# Led_Driver_90_B1.net
KiCad netlist of a schematic drawn in EAGLE
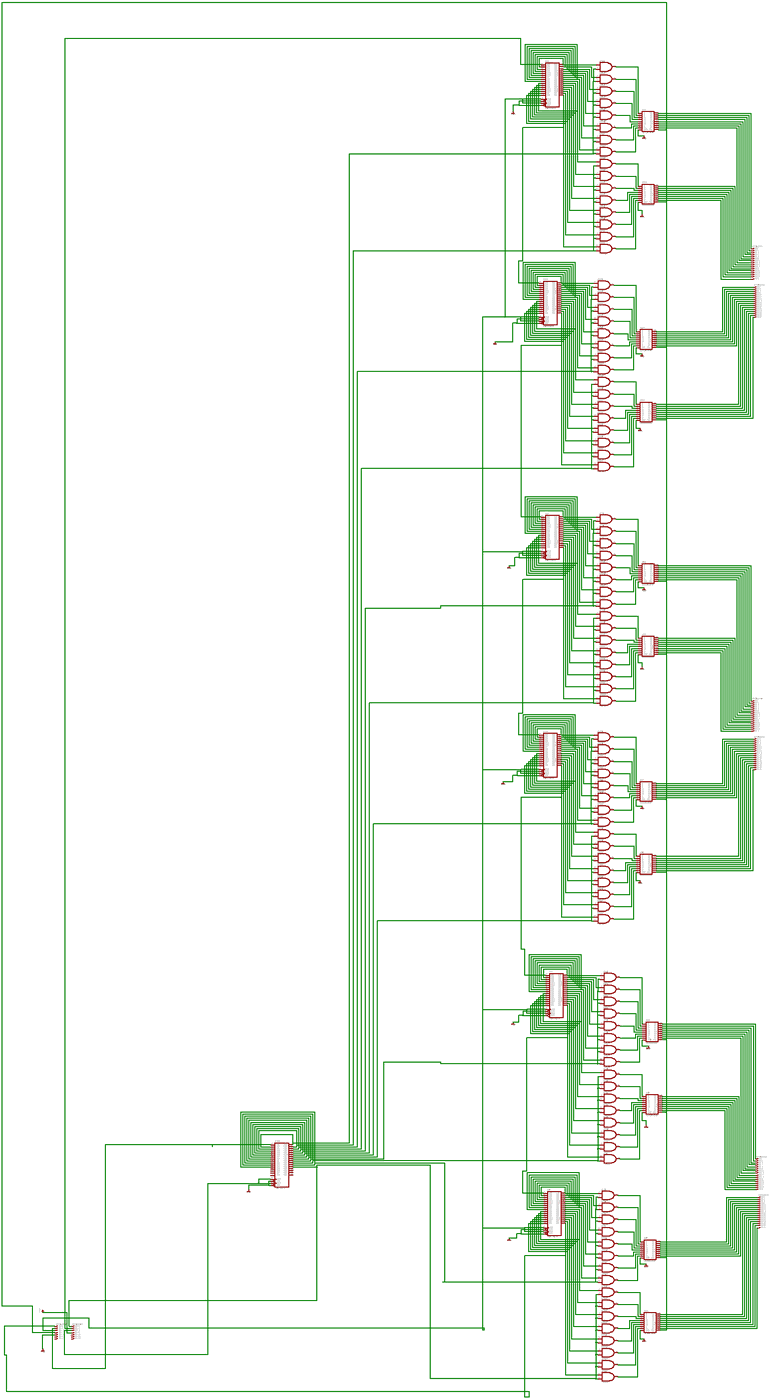
[diagram p0: schematic, sheet 1, overview]
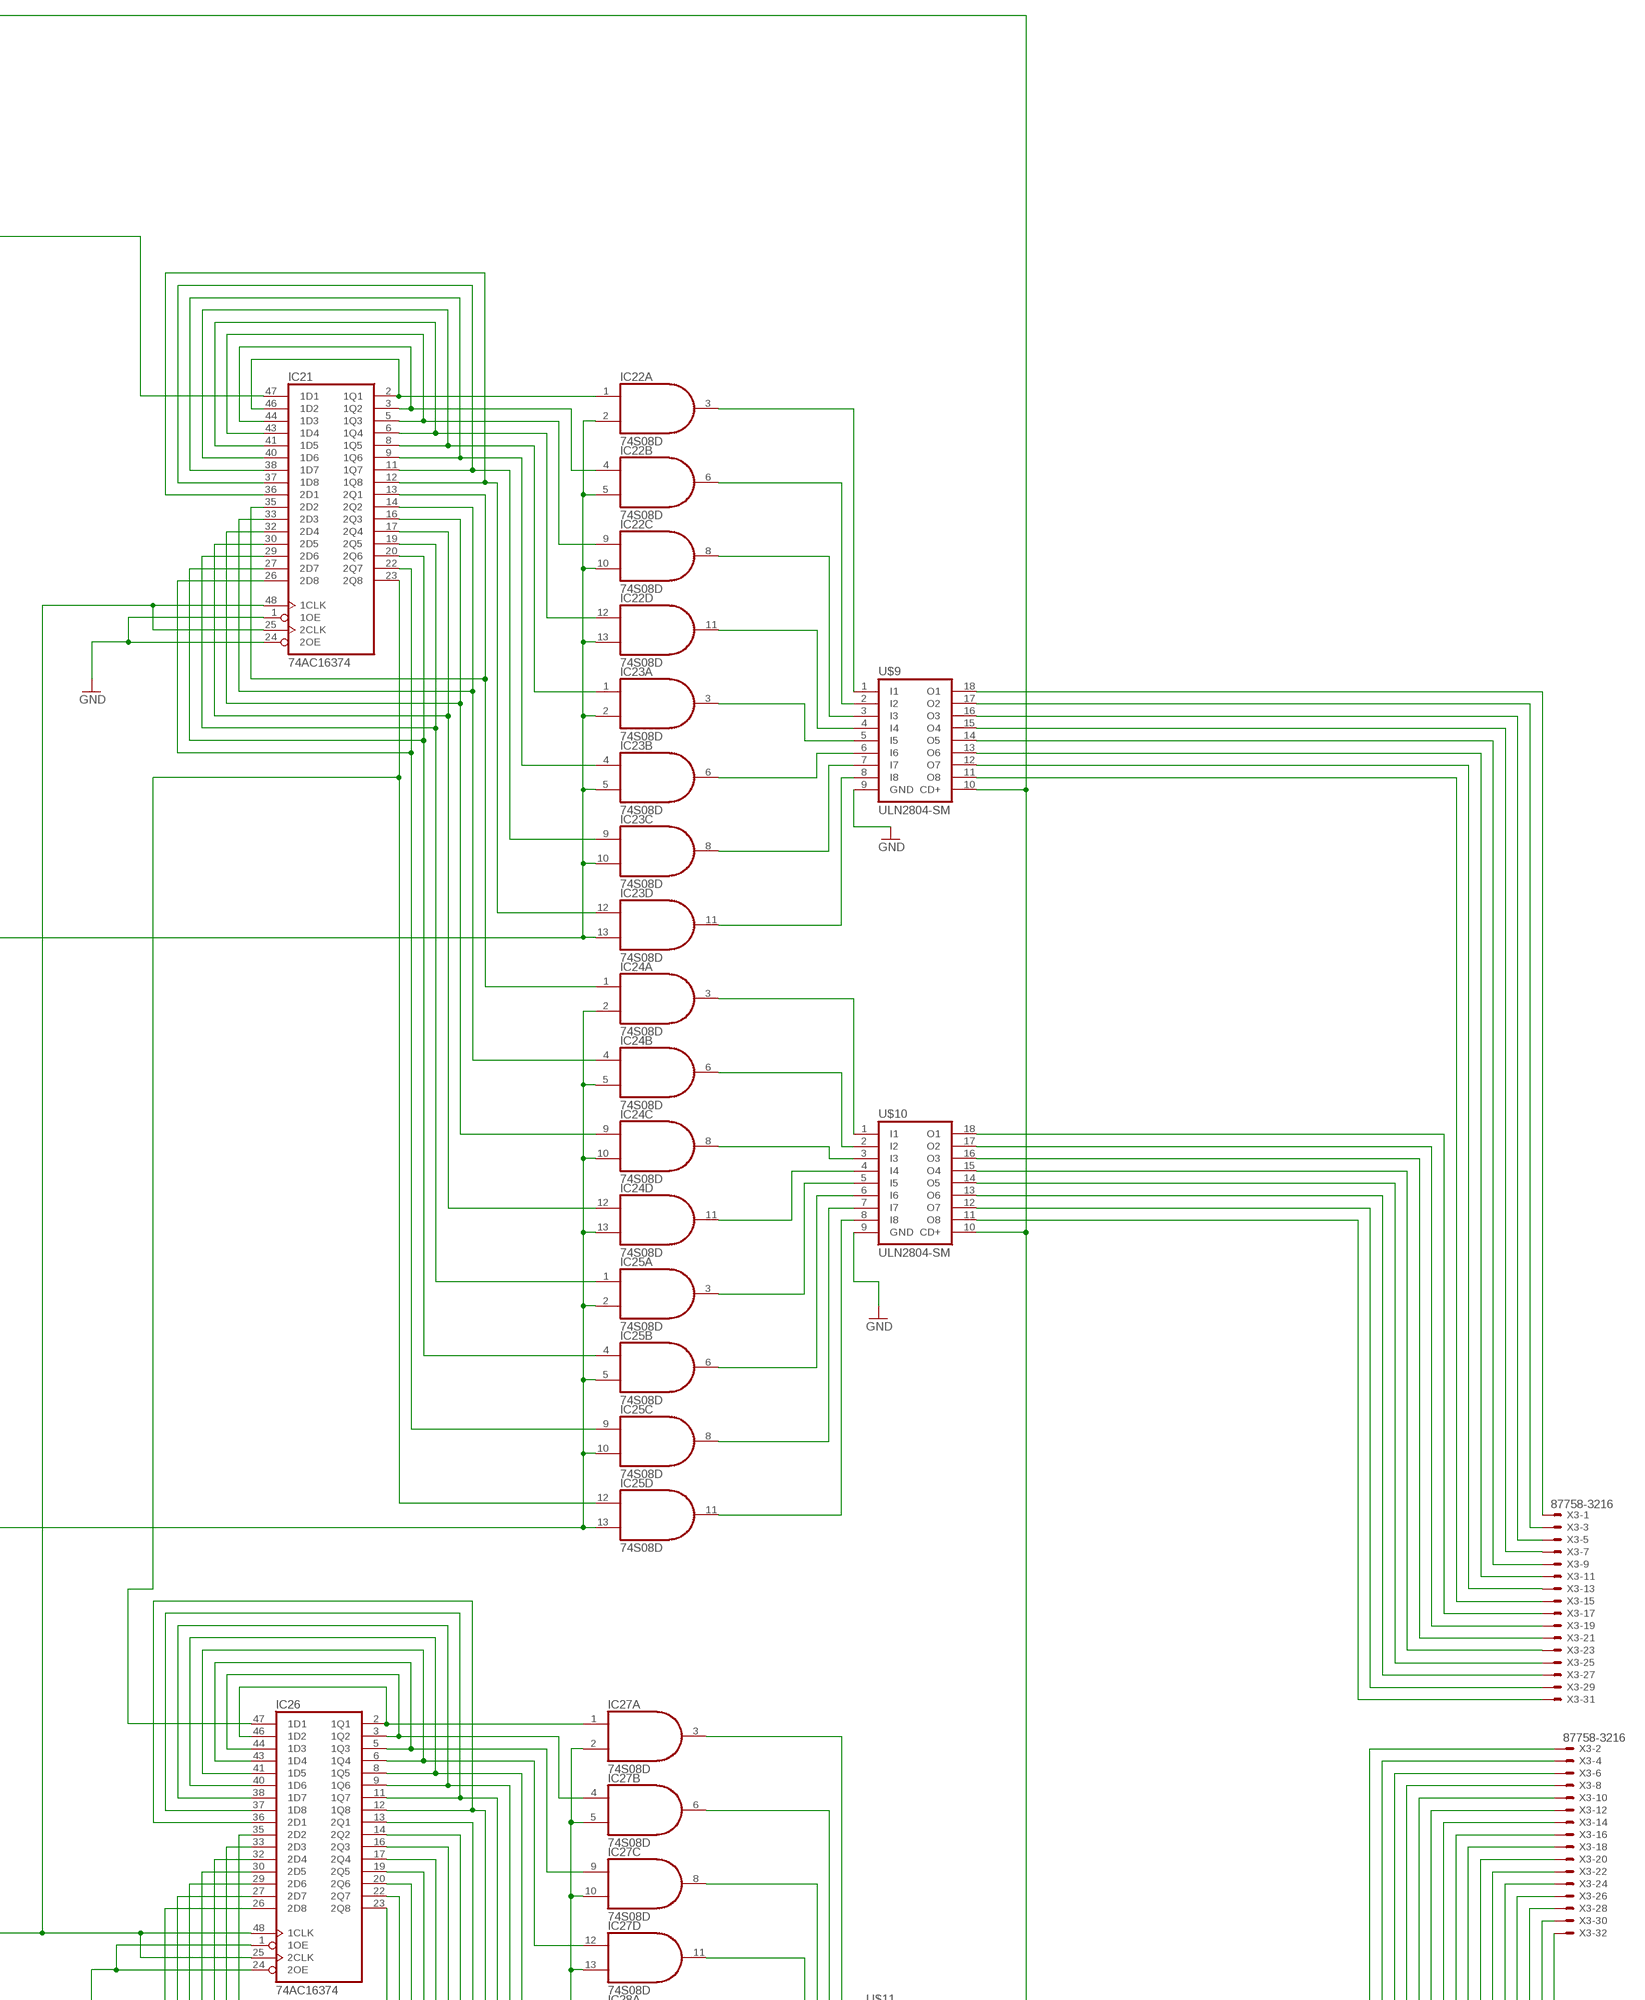
[diagram p1: schematic, sheet 1, part 1 of 9]
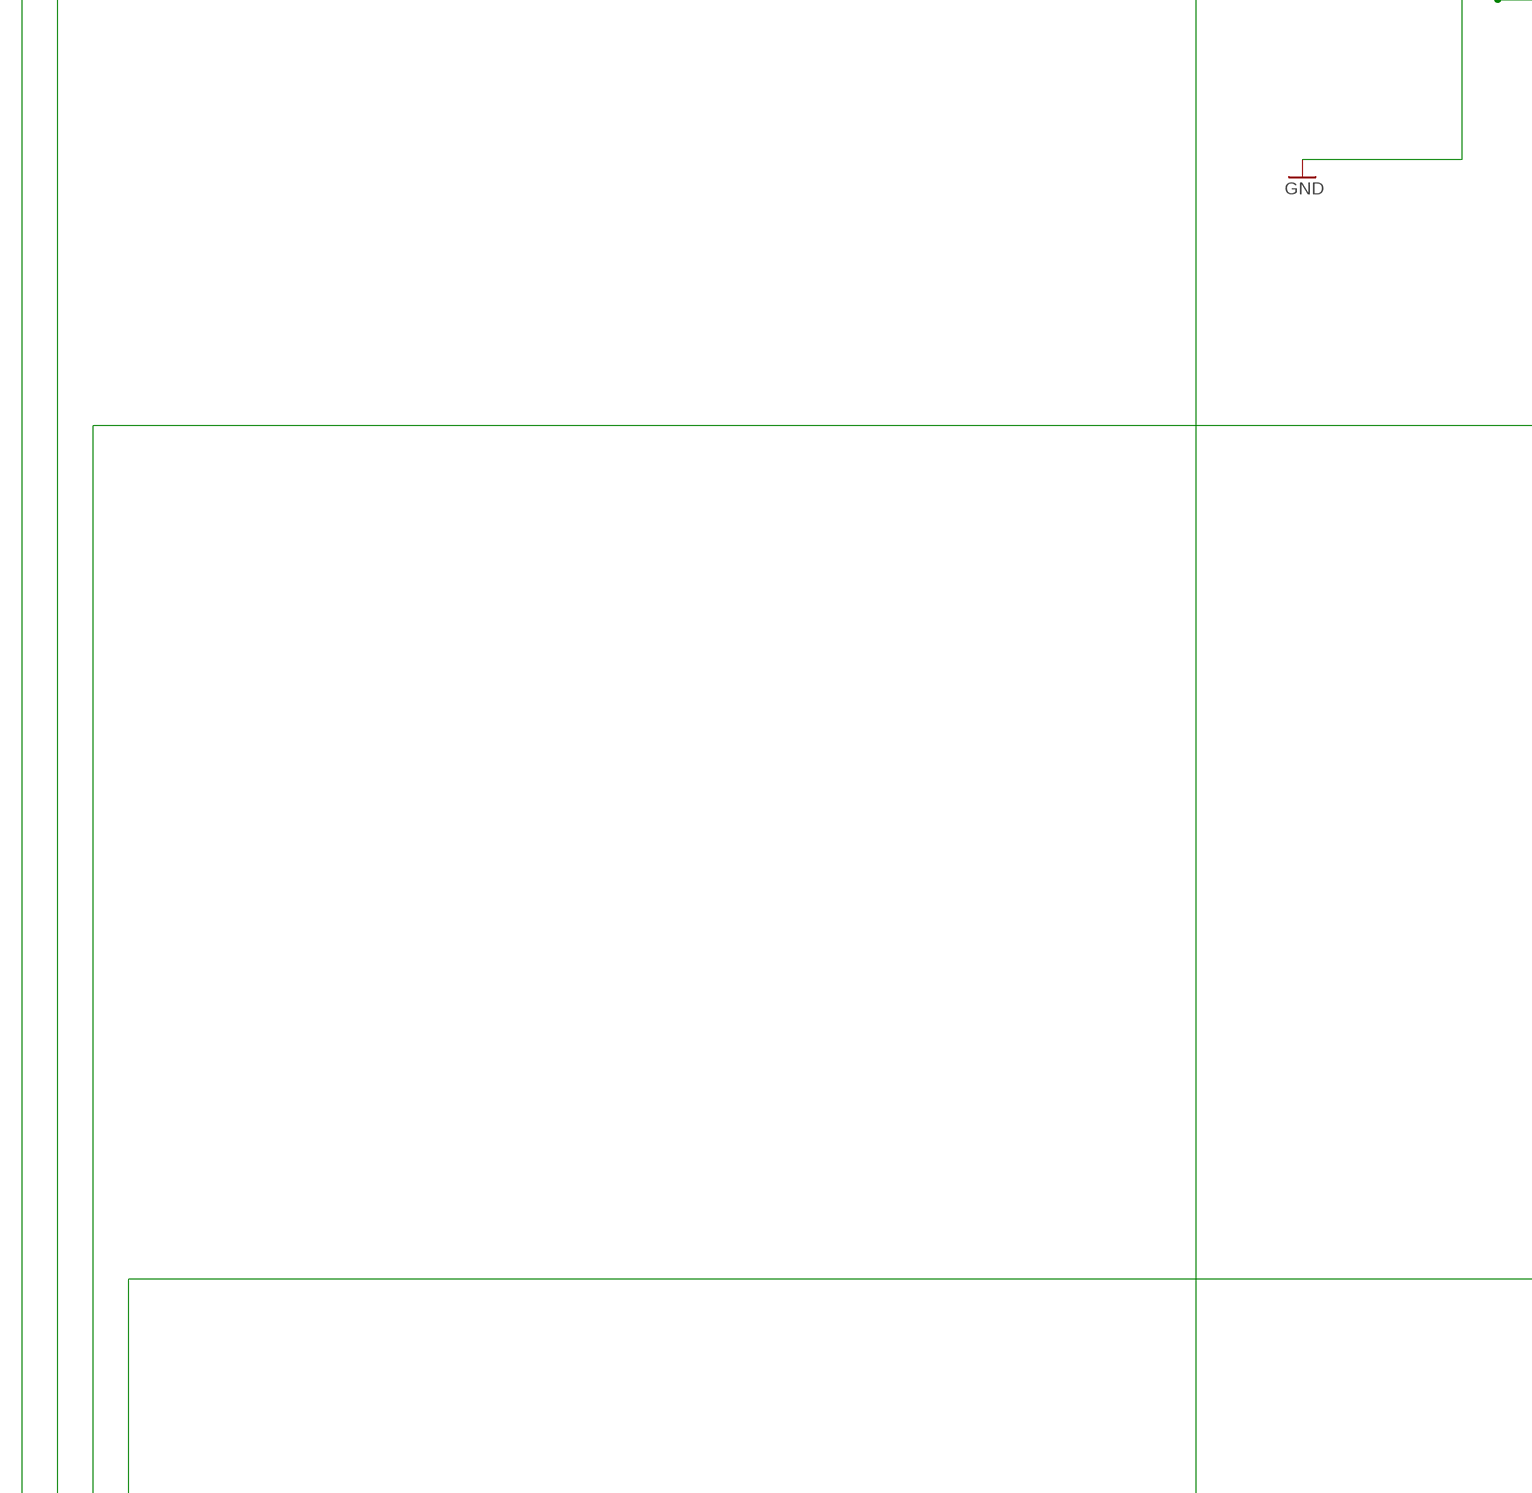
[diagram p2: schematic, sheet 1, part 2 of 9]
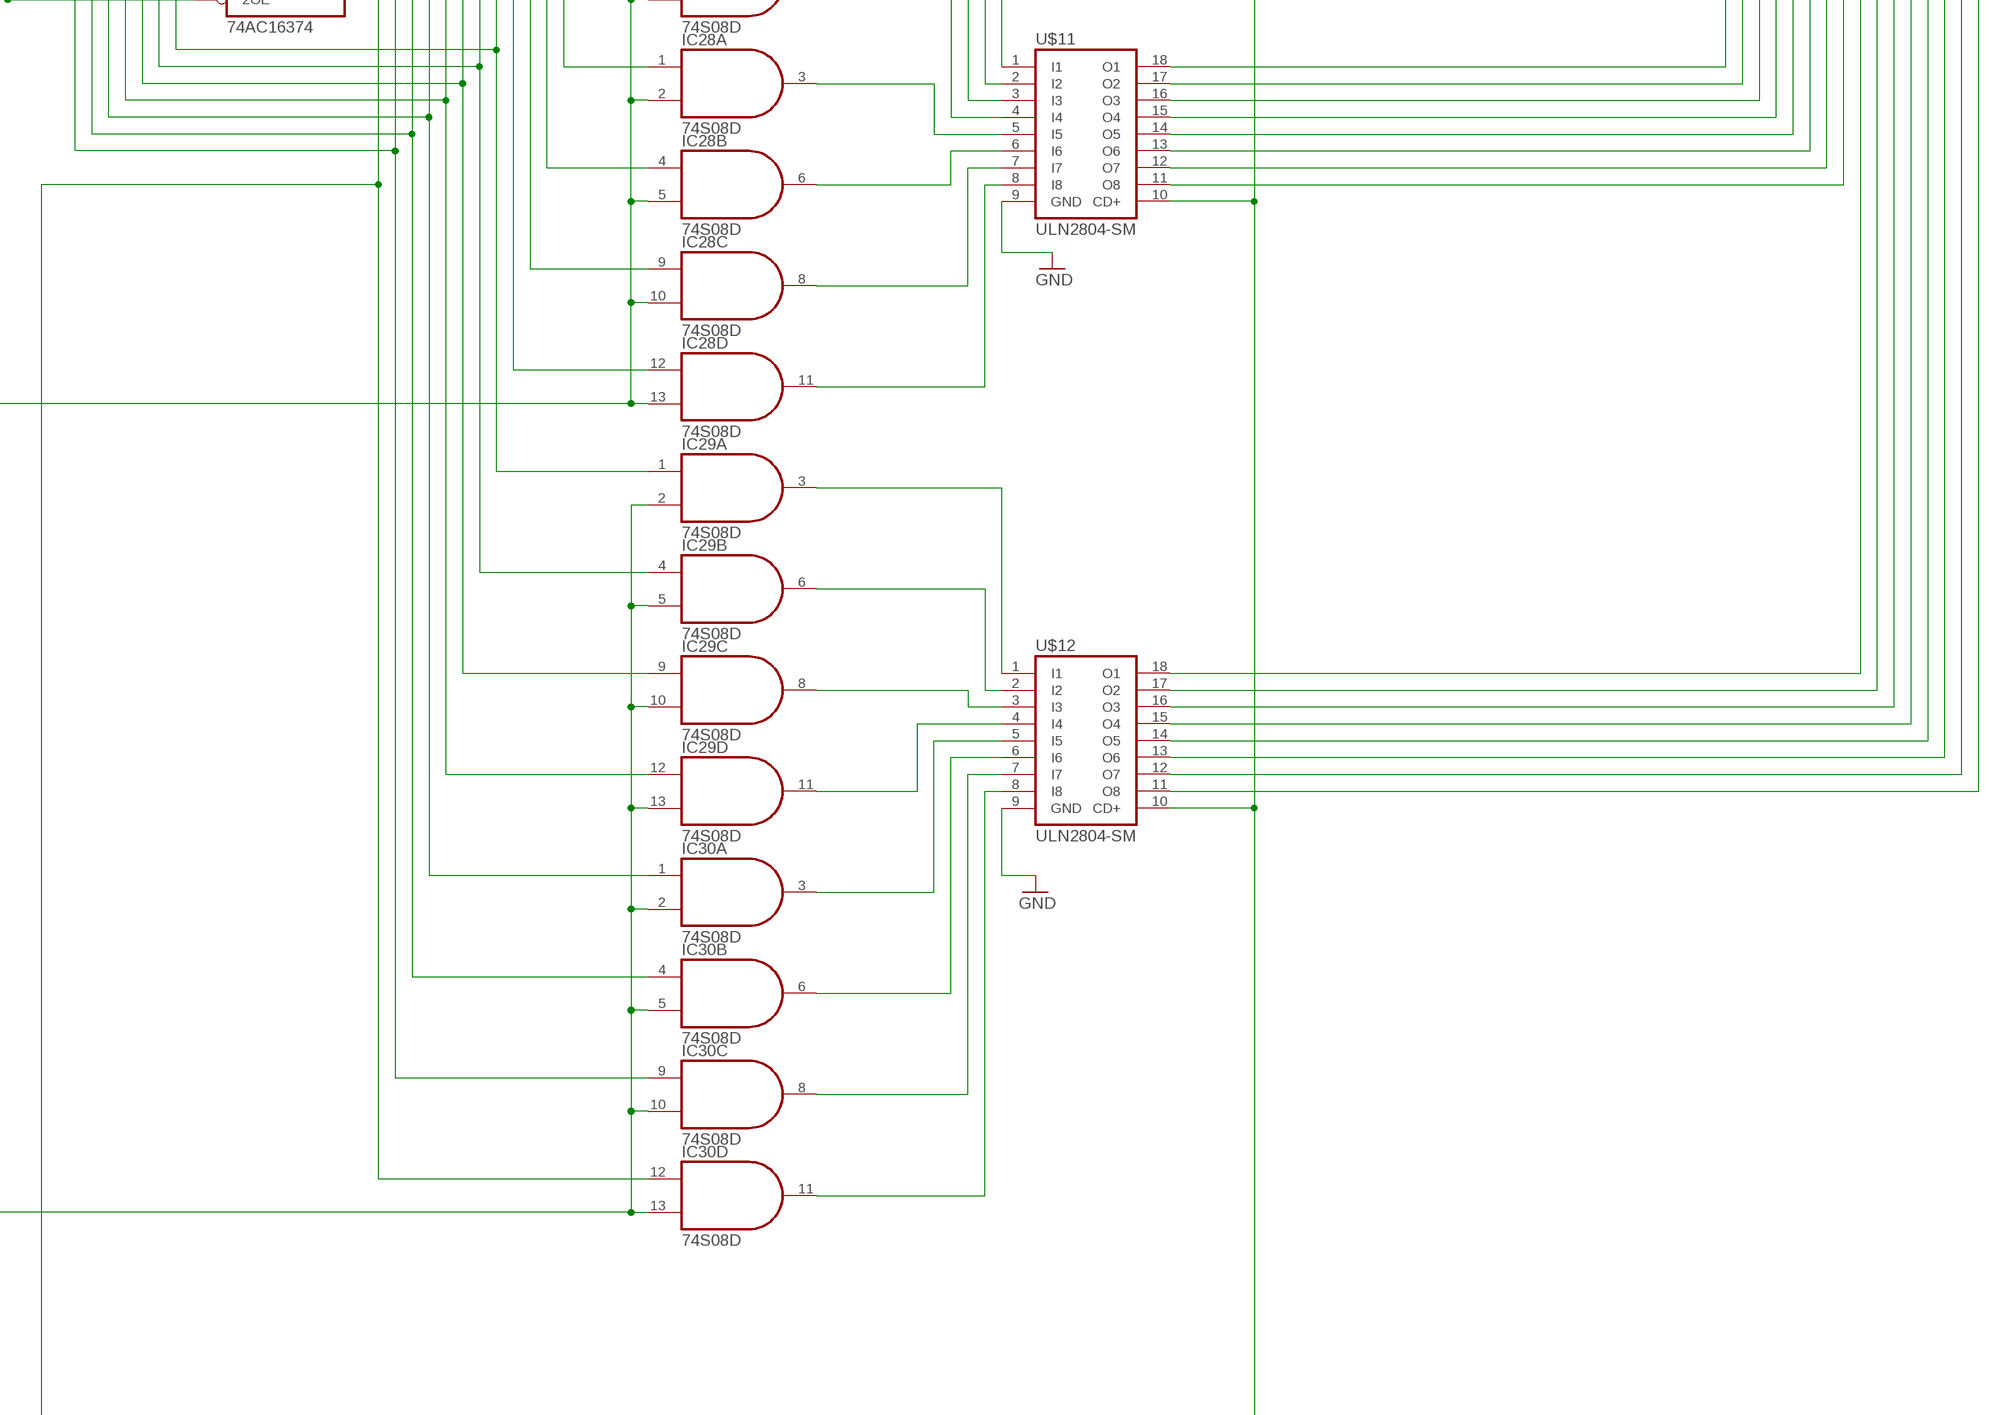
[diagram p3: schematic, sheet 1, part 3 of 9]
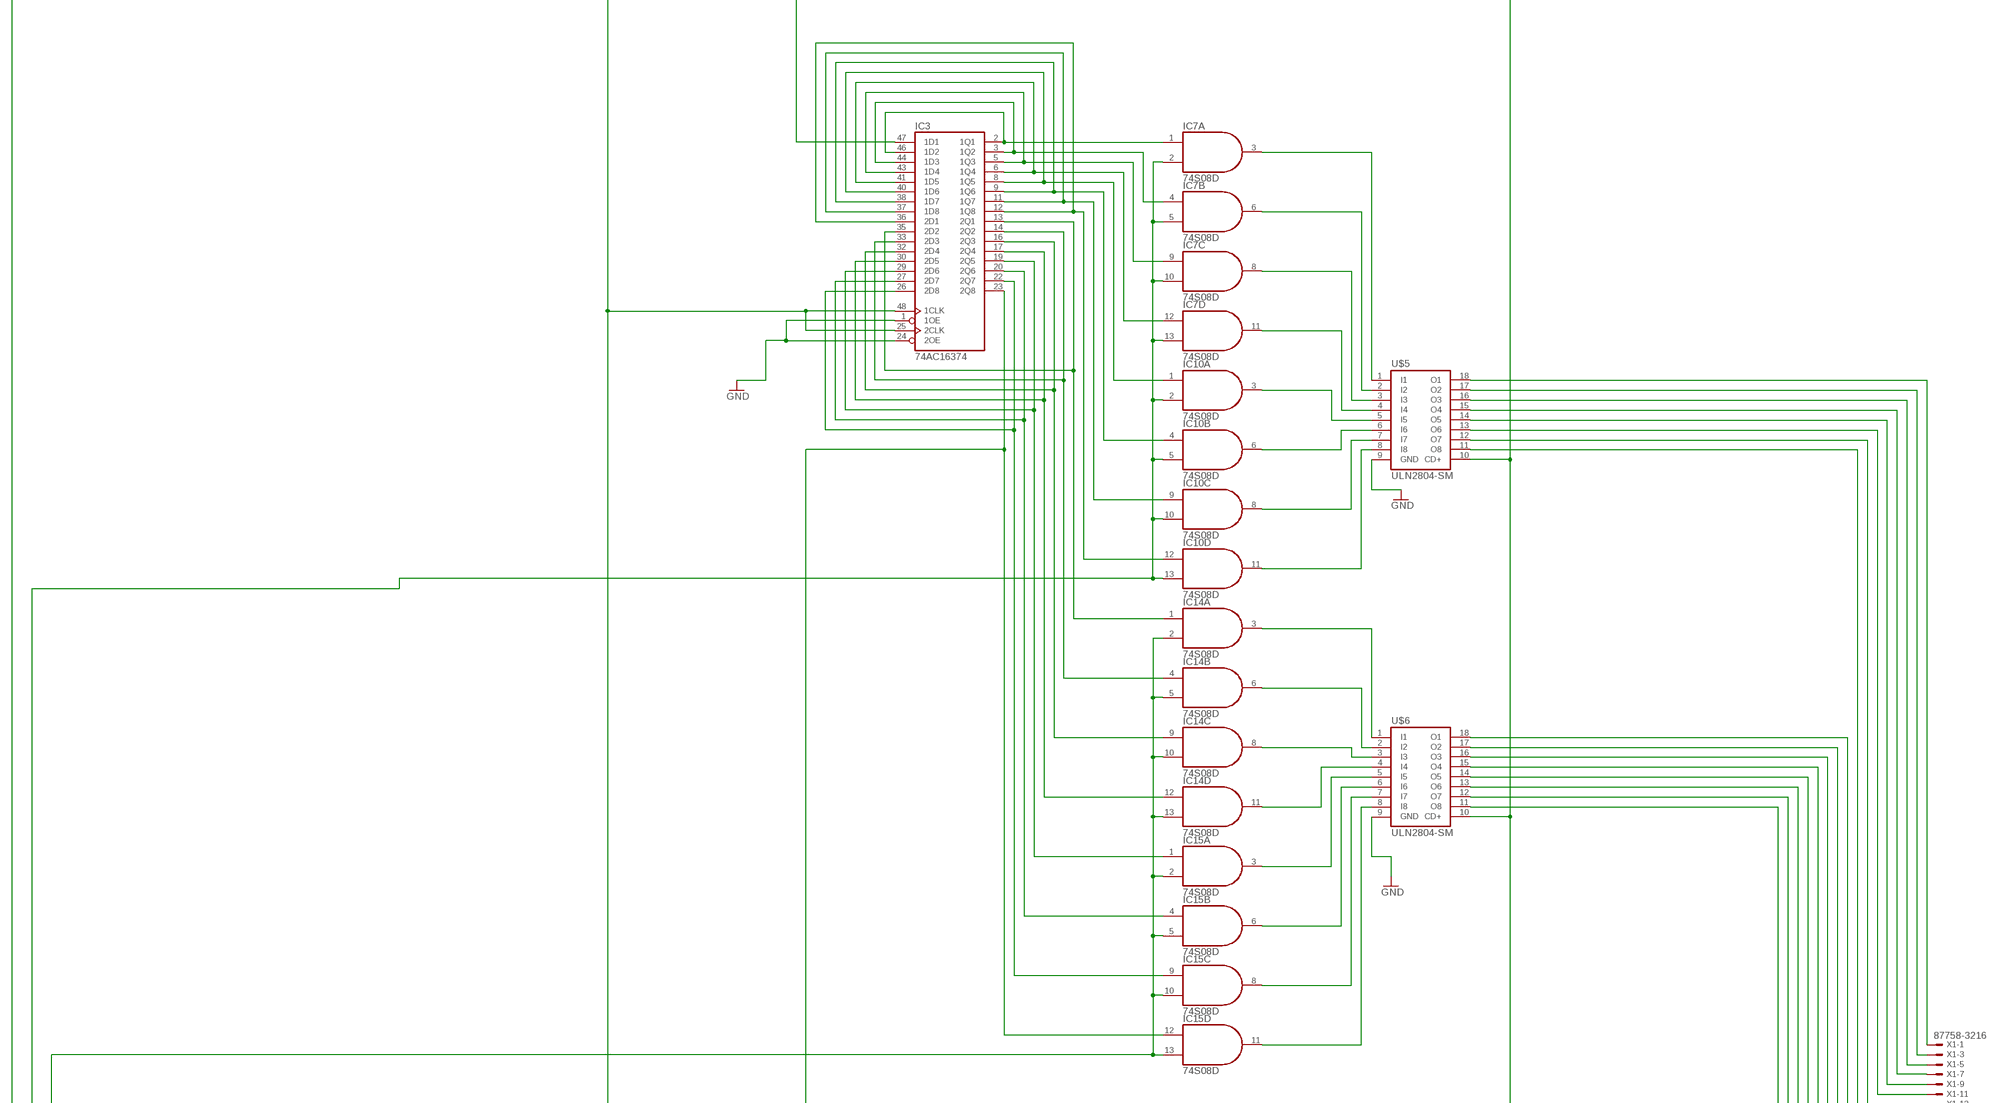
[diagram p4: schematic, sheet 1, part 4 of 9]
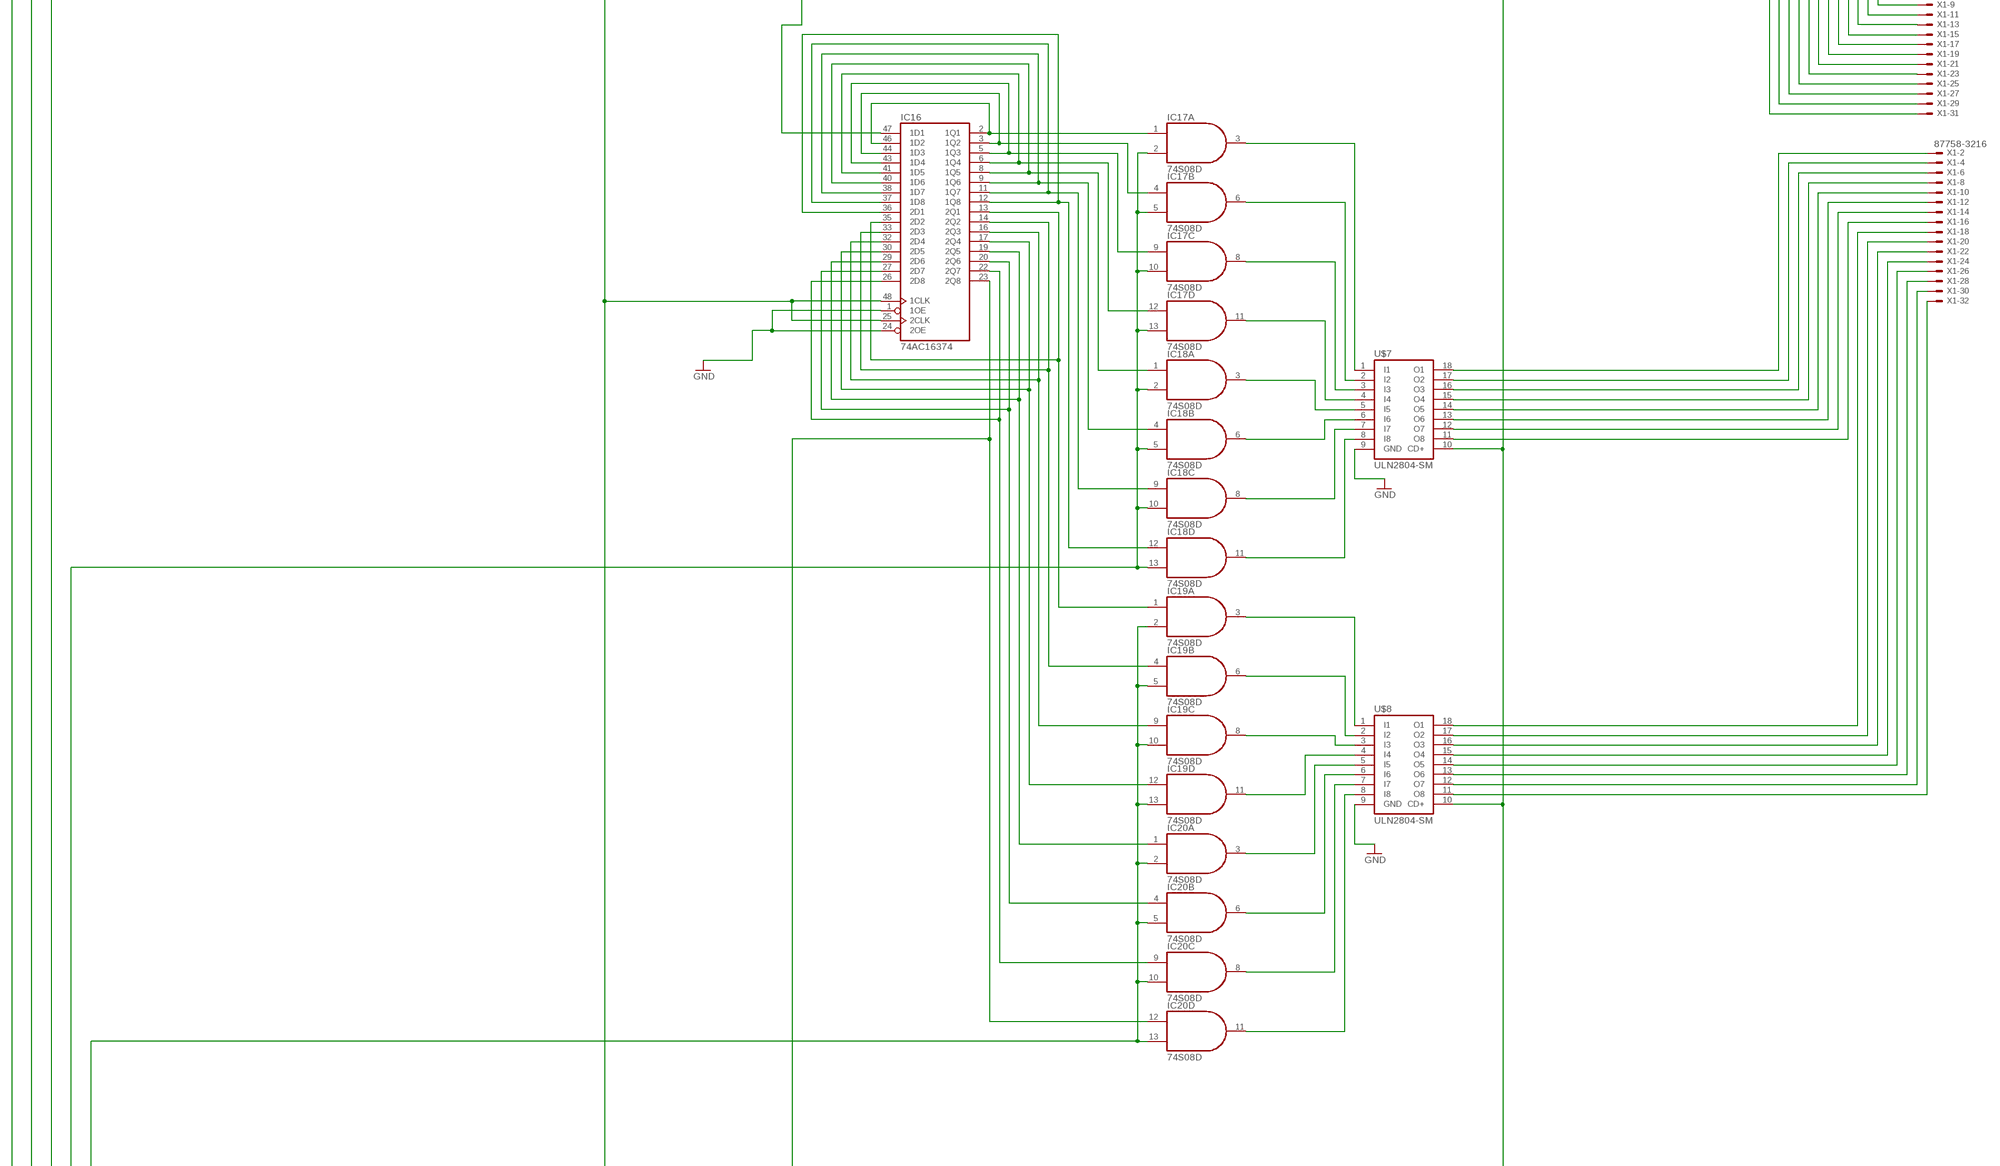
[diagram p5: schematic, sheet 1, part 5 of 9]
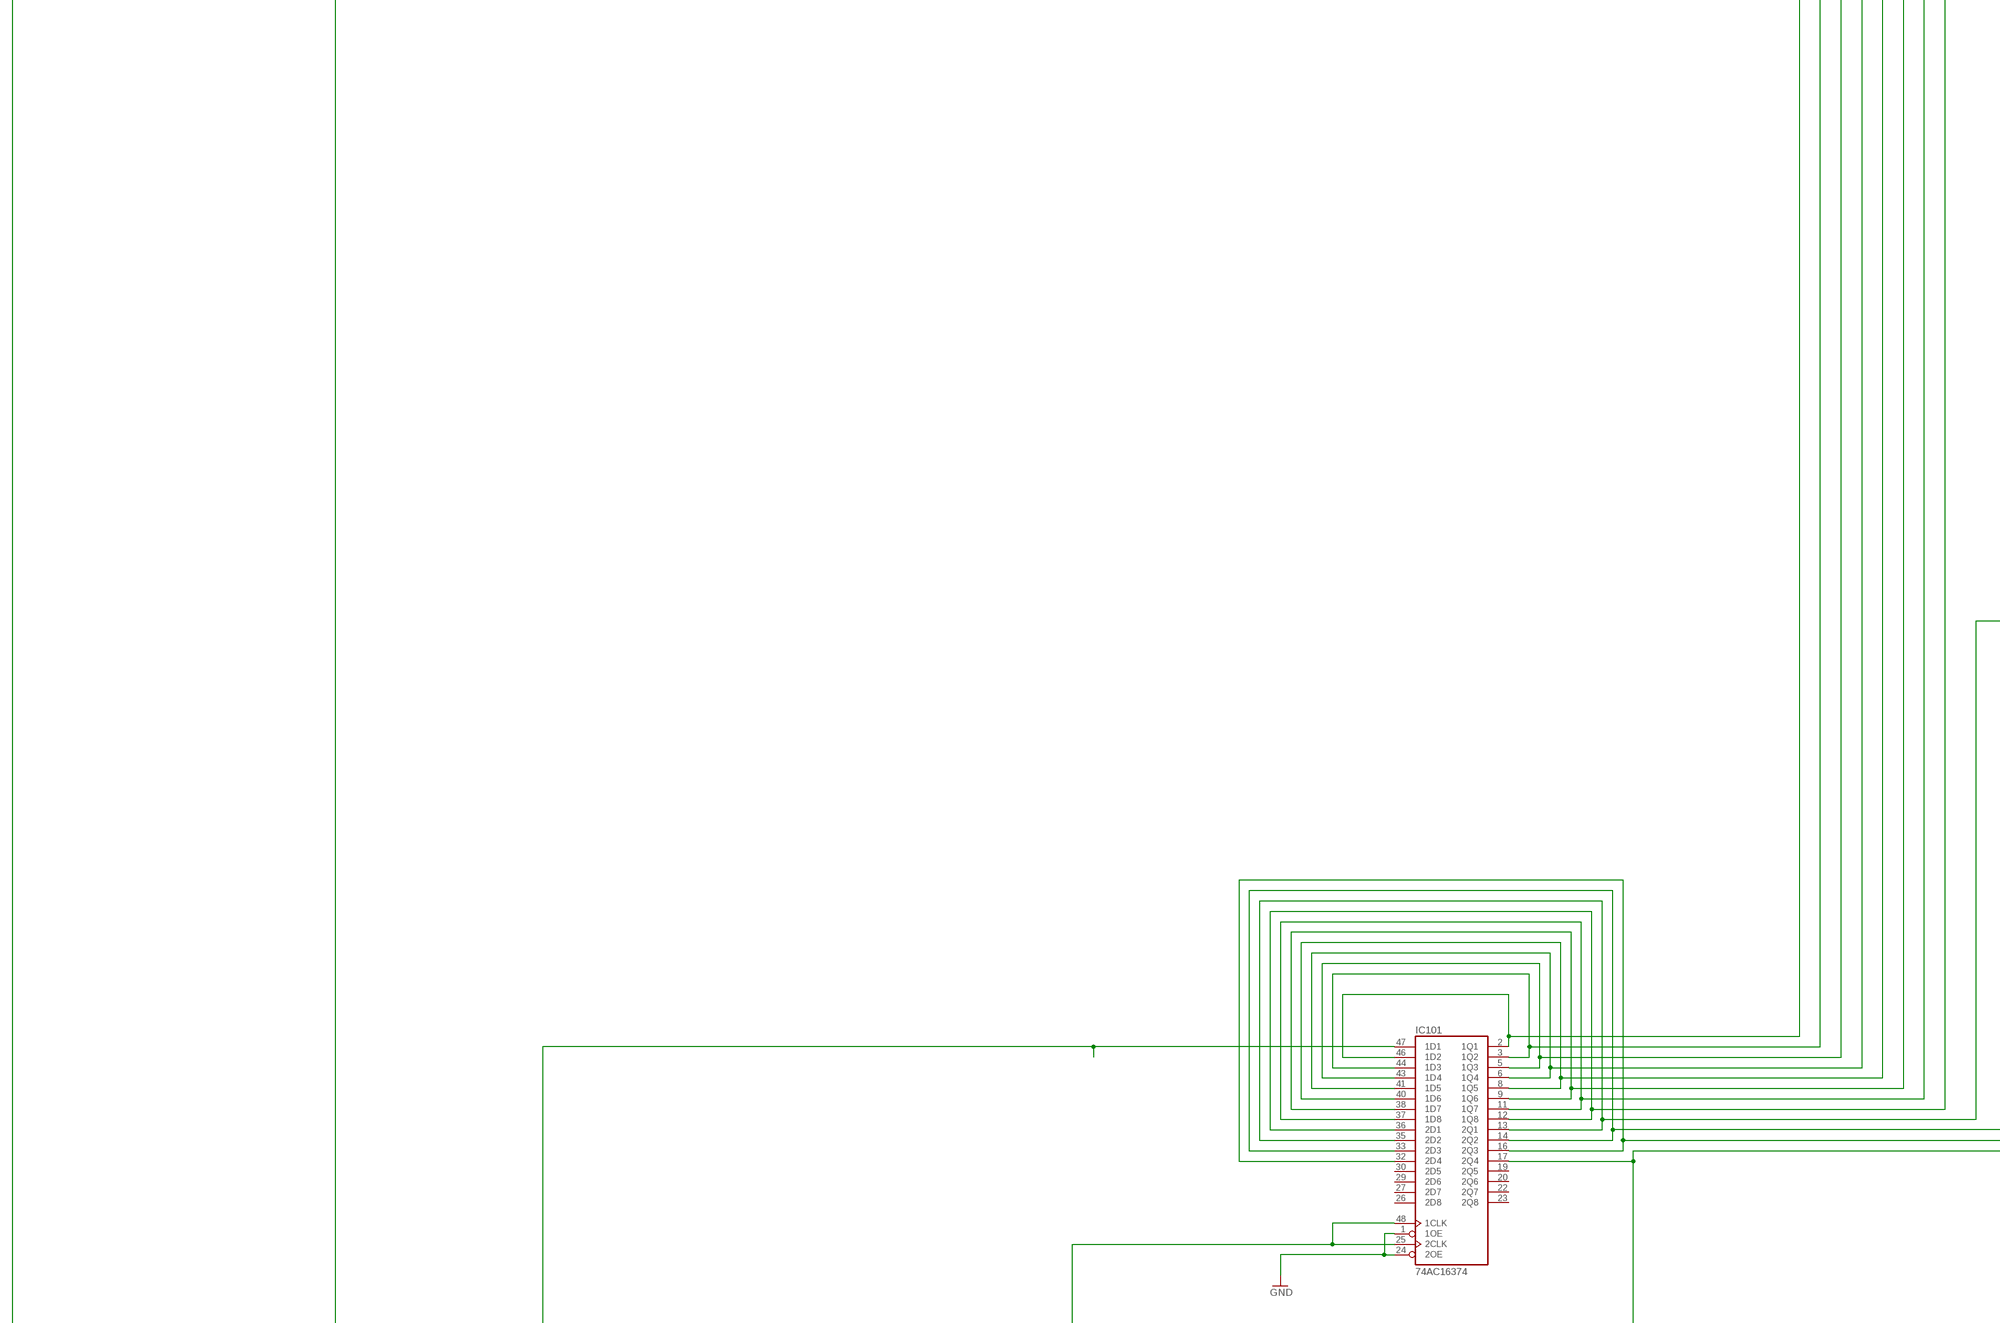
[diagram p6: schematic, sheet 1, part 6 of 9]
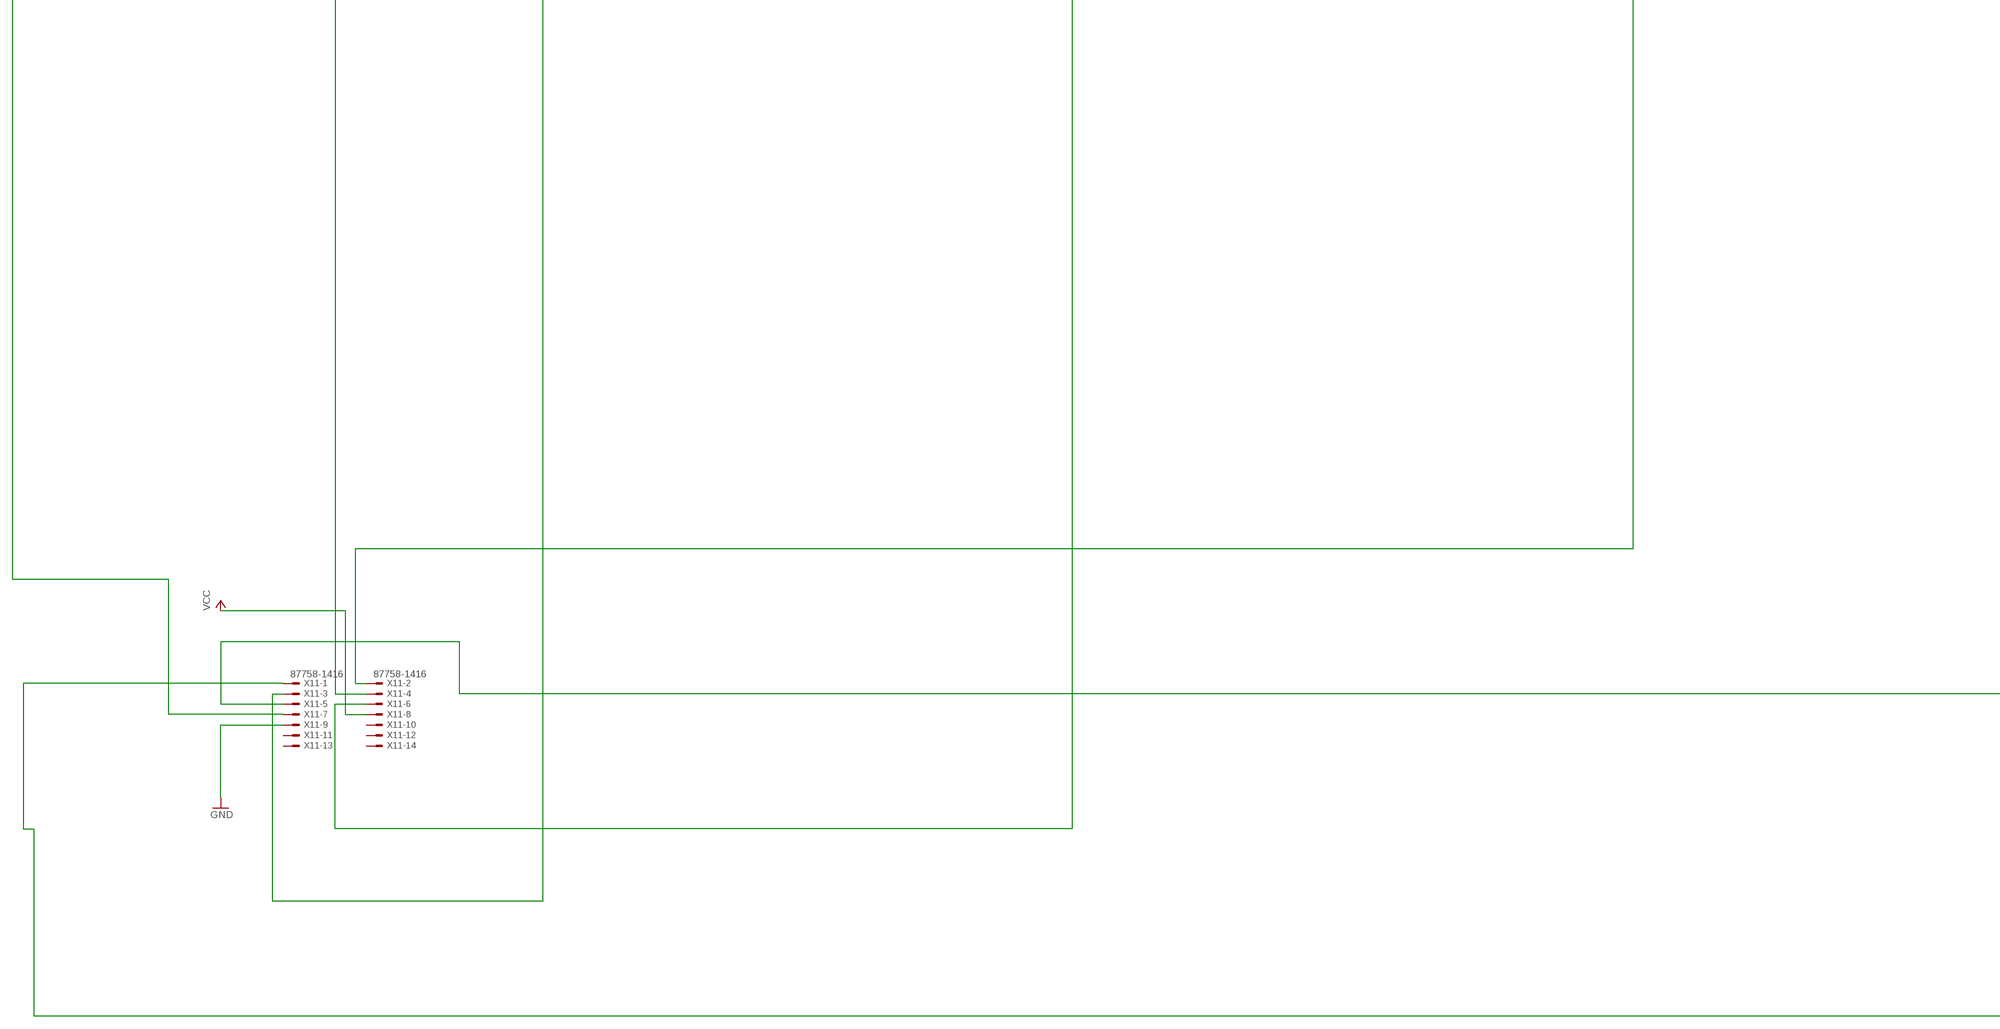
[diagram p7: schematic, sheet 1, part 7 of 9]
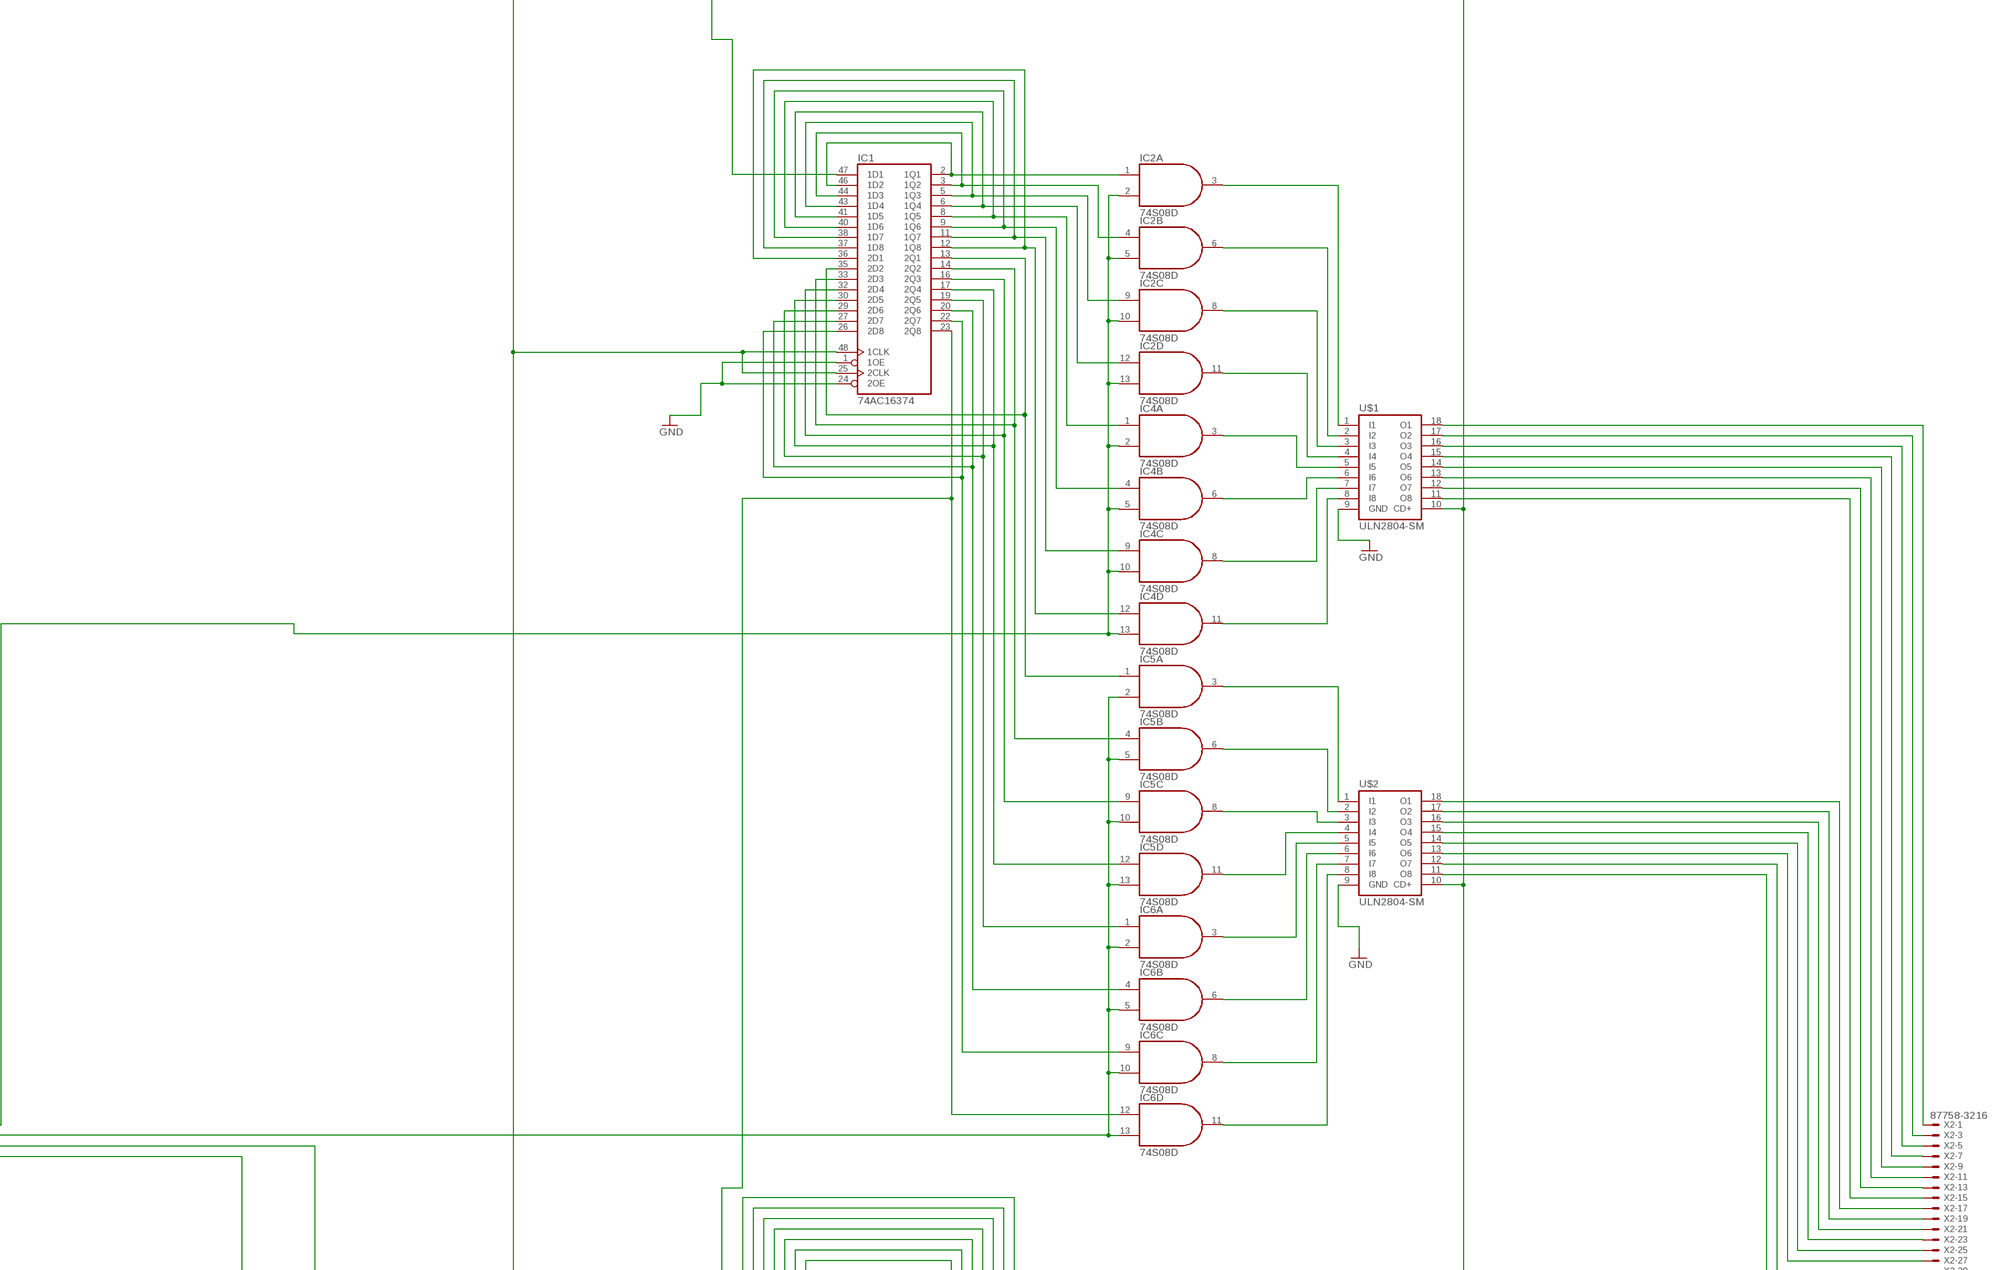
[diagram p8: schematic, sheet 1, part 8 of 9]
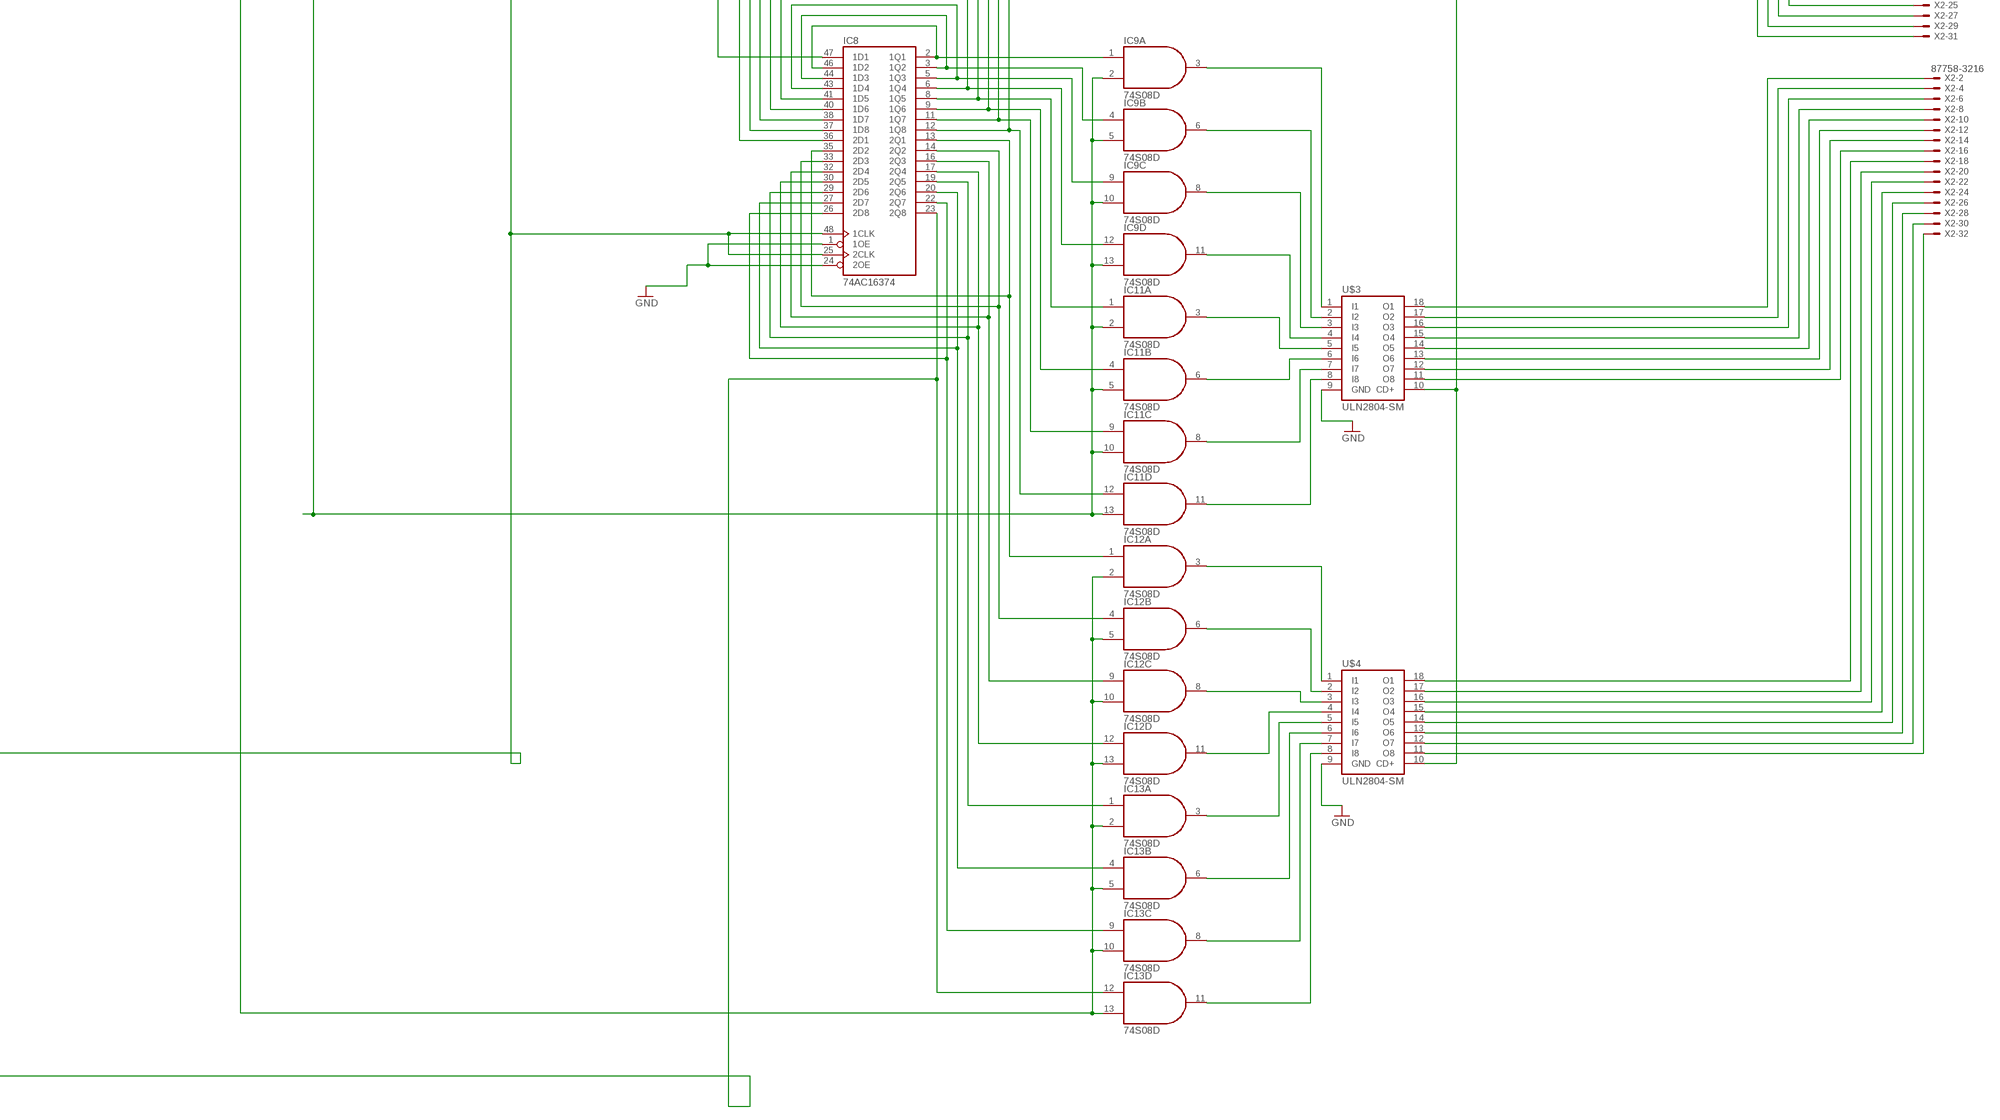
[diagram p9: schematic, sheet 1, part 9 of 9]

(export (version "E")
  (design (tool "Eeschema 10.0.6"))
  (components
    (comp (ref "IC1")
      (value "74AC16374")
      (footprint "eagle-import:SSOP48DL")
      (libsource (lib "eagle-import") (part "74AC16374"))
    )
    (comp (ref "IC2")
      (value "74S08D")
      (footprint "eagle-import:SO14")
      (libsource (lib "eagle-import") (part "7408DS"))
    )
    (comp (ref "IC3")
      (value "74AC16374")
      (footprint "eagle-import:SSOP48DL")
      (libsource (lib "eagle-import") (part "74AC16374"))
    )
    (comp (ref "IC4")
      (value "74S08D")
      (footprint "eagle-import:SO14")
      (libsource (lib "eagle-import") (part "7408DS"))
    )
    (comp (ref "IC5")
      (value "74S08D")
      (footprint "eagle-import:SO14")
      (libsource (lib "eagle-import") (part "7408DS"))
    )
    (comp (ref "IC6")
      (value "74S08D")
      (footprint "eagle-import:SO14")
      (libsource (lib "eagle-import") (part "7408DS"))
    )
    (comp (ref "IC7")
      (value "74S08D")
      (footprint "eagle-import:SO14")
      (libsource (lib "eagle-import") (part "7408DS"))
    )
    (comp (ref "IC8")
      (value "74AC16374")
      (footprint "eagle-import:SSOP48DL")
      (libsource (lib "eagle-import") (part "74AC16374"))
    )
    (comp (ref "IC9")
      (value "74S08D")
      (footprint "eagle-import:SO14")
      (libsource (lib "eagle-import") (part "7408DS"))
    )
    (comp (ref "IC10")
      (value "74S08D")
      (footprint "eagle-import:SO14")
      (libsource (lib "eagle-import") (part "7408DS"))
    )
    (comp (ref "IC11")
      (value "74S08D")
      (footprint "eagle-import:SO14")
      (libsource (lib "eagle-import") (part "7408DS"))
    )
    (comp (ref "IC12")
      (value "74S08D")
      (footprint "eagle-import:SO14")
      (libsource (lib "eagle-import") (part "7408DS"))
    )
    (comp (ref "IC13")
      (value "74S08D")
      (footprint "eagle-import:SO14")
      (libsource (lib "eagle-import") (part "7408DS"))
    )
    (comp (ref "IC14")
      (value "74S08D")
      (footprint "eagle-import:SO14")
      (libsource (lib "eagle-import") (part "7408DS"))
    )
    (comp (ref "IC15")
      (value "74S08D")
      (footprint "eagle-import:SO14")
      (libsource (lib "eagle-import") (part "7408DS"))
    )
    (comp (ref "IC16")
      (value "74AC16374")
      (footprint "eagle-import:SSOP48DL")
      (libsource (lib "eagle-import") (part "74AC16374"))
    )
    (comp (ref "IC17")
      (value "74S08D")
      (footprint "eagle-import:SO14")
      (libsource (lib "eagle-import") (part "7408DS"))
    )
    (comp (ref "IC18")
      (value "74S08D")
      (footprint "eagle-import:SO14")
      (libsource (lib "eagle-import") (part "7408DS"))
    )
    (comp (ref "IC19")
      (value "74S08D")
      (footprint "eagle-import:SO14")
      (libsource (lib "eagle-import") (part "7408DS"))
    )
    (comp (ref "IC20")
      (value "74S08D")
      (footprint "eagle-import:SO14")
      (libsource (lib "eagle-import") (part "7408DS"))
    )
    (comp (ref "IC21")
      (value "74AC16374")
      (footprint "eagle-import:SSOP48DL")
      (libsource (lib "eagle-import") (part "74AC16374"))
    )
    (comp (ref "IC22")
      (value "74S08D")
      (footprint "eagle-import:SO14")
      (libsource (lib "eagle-import") (part "7408DS"))
    )
    (comp (ref "IC23")
      (value "74S08D")
      (footprint "eagle-import:SO14")
      (libsource (lib "eagle-import") (part "7408DS"))
    )
    (comp (ref "IC24")
      (value "74S08D")
      (footprint "eagle-import:SO14")
      (libsource (lib "eagle-import") (part "7408DS"))
    )
    (comp (ref "IC25")
      (value "74S08D")
      (footprint "eagle-import:SO14")
      (libsource (lib "eagle-import") (part "7408DS"))
    )
    (comp (ref "IC26")
      (value "74AC16374")
      (footprint "eagle-import:SSOP48DL")
      (libsource (lib "eagle-import") (part "74AC16374"))
    )
    (comp (ref "IC27")
      (value "74S08D")
      (footprint "eagle-import:SO14")
      (libsource (lib "eagle-import") (part "7408DS"))
    )
    (comp (ref "IC28")
      (value "74S08D")
      (footprint "eagle-import:SO14")
      (libsource (lib "eagle-import") (part "7408DS"))
    )
    (comp (ref "IC29")
      (value "74S08D")
      (footprint "eagle-import:SO14")
      (libsource (lib "eagle-import") (part "7408DS"))
    )
    (comp (ref "IC30")
      (value "74S08D")
      (footprint "eagle-import:SO14")
      (libsource (lib "eagle-import") (part "7408DS"))
    )
    (comp (ref "IC101")
      (value "74AC16374")
      (footprint "eagle-import:SSOP48DL")
      (libsource (lib "eagle-import") (part "74AC16374"))
    )
    (comp (ref "U$1")
      (value "ULN2804-SM")
      (footprint "eagle-import:SOP-18")
      (libsource (lib "eagle-import") (part "ULN2804-SM"))
    )
    (comp (ref "U$2")
      (value "ULN2804-SM")
      (footprint "eagle-import:SOP-18")
      (libsource (lib "eagle-import") (part "ULN2804-SM"))
    )
    (comp (ref "U$3")
      (value "ULN2804-SM")
      (footprint "eagle-import:SOP-18")
      (libsource (lib "eagle-import") (part "ULN2804-SM"))
    )
    (comp (ref "U$4")
      (value "ULN2804-SM")
      (footprint "eagle-import:SOP-18")
      (libsource (lib "eagle-import") (part "ULN2804-SM"))
    )
    (comp (ref "U$5")
      (value "ULN2804-SM")
      (footprint "eagle-import:SOP-18")
      (libsource (lib "eagle-import") (part "ULN2804-SM"))
    )
    (comp (ref "U$6")
      (value "ULN2804-SM")
      (footprint "eagle-import:SOP-18")
      (libsource (lib "eagle-import") (part "ULN2804-SM"))
    )
    (comp (ref "U$7")
      (value "ULN2804-SM")
      (footprint "eagle-import:SOP-18")
      (libsource (lib "eagle-import") (part "ULN2804-SM"))
    )
    (comp (ref "U$8")
      (value "ULN2804-SM")
      (footprint "eagle-import:SOP-18")
      (libsource (lib "eagle-import") (part "ULN2804-SM"))
    )
    (comp (ref "U$9")
      (value "ULN2804-SM")
      (footprint "eagle-import:SOP-18")
      (libsource (lib "eagle-import") (part "ULN2804-SM"))
    )
    (comp (ref "U$10")
      (value "ULN2804-SM")
      (footprint "eagle-import:SOP-18")
      (libsource (lib "eagle-import") (part "ULN2804-SM"))
    )
    (comp (ref "U$11")
      (value "ULN2804-SM")
      (footprint "eagle-import:SOP-18")
      (libsource (lib "eagle-import") (part "ULN2804-SM"))
    )
    (comp (ref "U$12")
      (value "ULN2804-SM")
      (footprint "eagle-import:SOP-18")
      (libsource (lib "eagle-import") (part "ULN2804-SM"))
    )
    (comp (ref "X1")
      (value "87758-3216")
      (footprint "eagle-import:87758-3216")
      (libsource (lib "eagle-import") (part "87758-3216"))
    )
    (comp (ref "X2")
      (value "87758-3216")
      (footprint "eagle-import:87758-3216")
      (libsource (lib "eagle-import") (part "87758-3216"))
    )
    (comp (ref "X3")
      (value "87758-3216")
      (footprint "eagle-import:87758-3216")
      (libsource (lib "eagle-import") (part "87758-3216"))
    )
    (comp (ref "X11")
      (value "87758-1416")
      (footprint "eagle-import:87758-1416")
      (fields (field (name "MF") "MOLEX"))
      (libsource (lib "eagle-import") (part "87758-1416"))
    )
  )
  (nets
    (net (code "1") (name "GND") (class "Default")
      (node (ref "IC1") (pin "1") (pinfunction "1OE_1") (pintype "input"))
      (node (ref "IC1") (pin "24") (pinfunction "2OE_24") (pintype "input"))
      (node (ref "IC101") (pin "1") (pinfunction "1OE_1") (pintype "input"))
      (node (ref "IC101") (pin "24") (pinfunction "2OE_24") (pintype "input"))
      (node (ref "IC16") (pin "1") (pinfunction "1OE_1") (pintype "input"))
      (node (ref "IC16") (pin "24") (pinfunction "2OE_24") (pintype "input"))
      (node (ref "IC21") (pin "1") (pinfunction "1OE_1") (pintype "input"))
      (node (ref "IC21") (pin "24") (pinfunction "2OE_24") (pintype "input"))
      (node (ref "IC26") (pin "1") (pinfunction "1OE_1") (pintype "input"))
      (node (ref "IC26") (pin "24") (pinfunction "2OE_24") (pintype "input"))
      (node (ref "IC3") (pin "1") (pinfunction "1OE_1") (pintype "input"))
      (node (ref "IC3") (pin "24") (pinfunction "2OE_24") (pintype "input"))
      (node (ref "IC8") (pin "1") (pinfunction "1OE_1") (pintype "input"))
      (node (ref "IC8") (pin "24") (pinfunction "2OE_24") (pintype "input"))
      (node (ref "U$1") (pin "9") (pinfunction "GND_9") (pintype "power_in"))
      (node (ref "U$10") (pin "9") (pinfunction "GND_9") (pintype "power_in"))
      (node (ref "U$11") (pin "9") (pinfunction "GND_9") (pintype "power_in"))
      (node (ref "U$12") (pin "9") (pinfunction "GND_9") (pintype "power_in"))
      (node (ref "U$2") (pin "9") (pinfunction "GND_9") (pintype "power_in"))
      (node (ref "U$3") (pin "9") (pinfunction "GND_9") (pintype "power_in"))
      (node (ref "U$4") (pin "9") (pinfunction "GND_9") (pintype "power_in"))
      (node (ref "U$5") (pin "9") (pinfunction "GND_9") (pintype "power_in"))
      (node (ref "U$6") (pin "9") (pinfunction "GND_9") (pintype "power_in"))
      (node (ref "U$7") (pin "9") (pinfunction "GND_9") (pintype "power_in"))
      (node (ref "U$8") (pin "9") (pinfunction "GND_9") (pintype "power_in"))
      (node (ref "U$9") (pin "9") (pinfunction "GND_9") (pintype "power_in"))
      (node (ref "X11") (pin "9") (pinfunction "S_9") (pintype "passive"))
    )
    (net (code "2") (name "Net-(IC1A-1D2)") (class "Default")
      (node (ref "IC1") (pin "2") (pinfunction "1Q1_2") (pintype "tri_state"))
      (node (ref "IC1") (pin "46") (pinfunction "1D2_46") (pintype "input"))
      (node (ref "IC2") (pin "1") (pinfunction "I0_1") (pintype "input"))
    )
    (net (code "3") (name "Net-(IC1A-1D3)") (class "Default")
      (node (ref "IC1") (pin "3") (pinfunction "1Q2_3") (pintype "tri_state"))
      (node (ref "IC1") (pin "44") (pinfunction "1D3_44") (pintype "input"))
      (node (ref "IC2") (pin "4") (pinfunction "I0_4") (pintype "input"))
    )
    (net (code "4") (name "Net-(IC1A-1D4)") (class "Default")
      (node (ref "IC1") (pin "43") (pinfunction "1D4_43") (pintype "input"))
      (node (ref "IC1") (pin "5") (pinfunction "1Q3_5") (pintype "tri_state"))
      (node (ref "IC2") (pin "9") (pinfunction "I0_9") (pintype "input"))
    )
    (net (code "5") (name "Net-(IC1A-1D5)") (class "Default")
      (node (ref "IC1") (pin "41") (pinfunction "1D5_41") (pintype "input"))
      (node (ref "IC1") (pin "6") (pinfunction "1Q4_6") (pintype "tri_state"))
      (node (ref "IC2") (pin "12") (pinfunction "I0_12") (pintype "input"))
    )
    (net (code "6") (name "Net-(IC1A-1D6)") (class "Default")
      (node (ref "IC1") (pin "40") (pinfunction "1D6_40") (pintype "input"))
      (node (ref "IC1") (pin "8") (pinfunction "1Q5_8") (pintype "tri_state"))
      (node (ref "IC4") (pin "1") (pinfunction "I0_1") (pintype "input"))
    )
    (net (code "7") (name "Net-(IC1A-1D7)") (class "Default")
      (node (ref "IC1") (pin "38") (pinfunction "1D7_38") (pintype "input"))
      (node (ref "IC1") (pin "9") (pinfunction "1Q6_9") (pintype "tri_state"))
      (node (ref "IC4") (pin "4") (pinfunction "I0_4") (pintype "input"))
    )
    (net (code "8") (name "Net-(IC1A-1D8)") (class "Default")
      (node (ref "IC1") (pin "11") (pinfunction "1Q7_11") (pintype "tri_state"))
      (node (ref "IC1") (pin "37") (pinfunction "1D8_37") (pintype "input"))
      (node (ref "IC4") (pin "9") (pinfunction "I0_9") (pintype "input"))
    )
    (net (code "9") (name "Net-(IC1A-1Q8)") (class "Default")
      (node (ref "IC1") (pin "12") (pinfunction "1Q8_12") (pintype "tri_state"))
      (node (ref "IC1") (pin "36") (pinfunction "2D1_36") (pintype "input"))
      (node (ref "IC4") (pin "12") (pinfunction "I0_12") (pintype "input"))
    )
    (net (code "10") (name "Net-(IC1A-2D2)") (class "Default")
      (node (ref "IC1") (pin "13") (pinfunction "2Q1_13") (pintype "tri_state"))
      (node (ref "IC1") (pin "35") (pinfunction "2D2_35") (pintype "input"))
      (node (ref "IC5") (pin "1") (pinfunction "I0_1") (pintype "input"))
    )
    (net (code "11") (name "Net-(IC1A-2D3)") (class "Default")
      (node (ref "IC1") (pin "14") (pinfunction "2Q2_14") (pintype "tri_state"))
      (node (ref "IC1") (pin "33") (pinfunction "2D3_33") (pintype "input"))
      (node (ref "IC5") (pin "4") (pinfunction "I0_4") (pintype "input"))
    )
    (net (code "12") (name "Net-(IC1A-2D4)") (class "Default")
      (node (ref "IC1") (pin "16") (pinfunction "2Q3_16") (pintype "tri_state"))
      (node (ref "IC1") (pin "32") (pinfunction "2D4_32") (pintype "input"))
      (node (ref "IC5") (pin "9") (pinfunction "I0_9") (pintype "input"))
    )
    (net (code "13") (name "Net-(IC1A-2D5)") (class "Default")
      (node (ref "IC1") (pin "17") (pinfunction "2Q4_17") (pintype "tri_state"))
      (node (ref "IC1") (pin "30") (pinfunction "2D5_30") (pintype "input"))
      (node (ref "IC5") (pin "12") (pinfunction "I0_12") (pintype "input"))
    )
    (net (code "14") (name "Net-(IC1A-2D6)") (class "Default")
      (node (ref "IC1") (pin "19") (pinfunction "2Q5_19") (pintype "tri_state"))
      (node (ref "IC1") (pin "29") (pinfunction "2D6_29") (pintype "input"))
      (node (ref "IC6") (pin "1") (pinfunction "I0_1") (pintype "input"))
    )
    (net (code "15") (name "Net-(IC1A-2D7)") (class "Default")
      (node (ref "IC1") (pin "20") (pinfunction "2Q6_20") (pintype "tri_state"))
      (node (ref "IC1") (pin "27") (pinfunction "2D7_27") (pintype "input"))
      (node (ref "IC6") (pin "4") (pinfunction "I0_4") (pintype "input"))
    )
    (net (code "16") (name "Net-(IC1A-2D8)") (class "Default")
      (node (ref "IC1") (pin "22") (pinfunction "2Q7_22") (pintype "tri_state"))
      (node (ref "IC1") (pin "26") (pinfunction "2D8_26") (pintype "input"))
      (node (ref "IC6") (pin "9") (pinfunction "I0_9") (pintype "input"))
    )
    (net (code "17") (name "Net-(IC1A-2Q8)") (class "Default")
      (node (ref "IC1") (pin "23") (pinfunction "2Q8_23") (pintype "tri_state"))
      (node (ref "IC6") (pin "12") (pinfunction "I0_12") (pintype "input"))
      (node (ref "IC8") (pin "47") (pinfunction "1D1_47") (pintype "input"))
    )
    (net (code "18") (name "Net-(IC2A-O)") (class "Default")
      (node (ref "IC2") (pin "3") (pinfunction "O_3") (pintype "output"))
      (node (ref "U$1") (pin "1") (pinfunction "I1_1") (pintype "input"))
    )
    (net (code "19") (name "Net-(IC2B-O)") (class "Default")
      (node (ref "IC2") (pin "6") (pinfunction "O_6") (pintype "output"))
      (node (ref "U$1") (pin "2") (pinfunction "I2_2") (pintype "input"))
    )
    (net (code "20") (name "Net-(IC2C-O)") (class "Default")
      (node (ref "IC2") (pin "8") (pinfunction "O_8") (pintype "output"))
      (node (ref "U$1") (pin "3") (pinfunction "I3_3") (pintype "input"))
    )
    (net (code "21") (name "Net-(IC2D-O)") (class "Default")
      (node (ref "IC2") (pin "11") (pinfunction "O_11") (pintype "output"))
      (node (ref "U$1") (pin "4") (pinfunction "I4_4") (pintype "input"))
    )
    (net (code "22") (name "Net-(IC3A-1D2)") (class "Default")
      (node (ref "IC3") (pin "2") (pinfunction "1Q1_2") (pintype "tri_state"))
      (node (ref "IC3") (pin "46") (pinfunction "1D2_46") (pintype "input"))
      (node (ref "IC7") (pin "1") (pinfunction "I0_1") (pintype "input"))
    )
    (net (code "23") (name "Net-(IC3A-1D3)") (class "Default")
      (node (ref "IC3") (pin "3") (pinfunction "1Q2_3") (pintype "tri_state"))
      (node (ref "IC3") (pin "44") (pinfunction "1D3_44") (pintype "input"))
      (node (ref "IC7") (pin "4") (pinfunction "I0_4") (pintype "input"))
    )
    (net (code "24") (name "Net-(IC3A-1D4)") (class "Default")
      (node (ref "IC3") (pin "43") (pinfunction "1D4_43") (pintype "input"))
      (node (ref "IC3") (pin "5") (pinfunction "1Q3_5") (pintype "tri_state"))
      (node (ref "IC7") (pin "9") (pinfunction "I0_9") (pintype "input"))
    )
    (net (code "25") (name "Net-(IC3A-1D5)") (class "Default")
      (node (ref "IC3") (pin "41") (pinfunction "1D5_41") (pintype "input"))
      (node (ref "IC3") (pin "6") (pinfunction "1Q4_6") (pintype "tri_state"))
      (node (ref "IC7") (pin "12") (pinfunction "I0_12") (pintype "input"))
    )
    (net (code "26") (name "Net-(IC4A-O)") (class "Default")
      (node (ref "IC4") (pin "3") (pinfunction "O_3") (pintype "output"))
      (node (ref "U$1") (pin "5") (pinfunction "I5_5") (pintype "input"))
    )
    (net (code "27") (name "Net-(IC4B-O)") (class "Default")
      (node (ref "IC4") (pin "6") (pinfunction "O_6") (pintype "output"))
      (node (ref "U$1") (pin "6") (pinfunction "I6_6") (pintype "input"))
    )
    (net (code "28") (name "Net-(IC4C-O)") (class "Default")
      (node (ref "IC4") (pin "8") (pinfunction "O_8") (pintype "output"))
      (node (ref "U$1") (pin "7") (pinfunction "I7_7") (pintype "input"))
    )
    (net (code "29") (name "Net-(IC4D-O)") (class "Default")
      (node (ref "IC4") (pin "11") (pinfunction "O_11") (pintype "output"))
      (node (ref "U$1") (pin "8") (pinfunction "I8_8") (pintype "input"))
    )
    (net (code "30") (name "Net-(IC5A-O)") (class "Default")
      (node (ref "IC5") (pin "3") (pinfunction "O_3") (pintype "output"))
      (node (ref "U$2") (pin "1") (pinfunction "I1_1") (pintype "input"))
    )
    (net (code "31") (name "Net-(IC5B-O)") (class "Default")
      (node (ref "IC5") (pin "6") (pinfunction "O_6") (pintype "output"))
      (node (ref "U$2") (pin "2") (pinfunction "I2_2") (pintype "input"))
    )
    (net (code "32") (name "Net-(IC5C-O)") (class "Default")
      (node (ref "IC5") (pin "8") (pinfunction "O_8") (pintype "output"))
      (node (ref "U$2") (pin "3") (pinfunction "I3_3") (pintype "input"))
    )
    (net (code "33") (name "Net-(IC5D-O)") (class "Default")
      (node (ref "IC5") (pin "11") (pinfunction "O_11") (pintype "output"))
      (node (ref "U$2") (pin "4") (pinfunction "I4_4") (pintype "input"))
    )
    (net (code "34") (name "Net-(IC6A-O)") (class "Default")
      (node (ref "IC6") (pin "3") (pinfunction "O_3") (pintype "output"))
      (node (ref "U$2") (pin "5") (pinfunction "I5_5") (pintype "input"))
    )
    (net (code "35") (name "Net-(IC6B-O)") (class "Default")
      (node (ref "IC6") (pin "6") (pinfunction "O_6") (pintype "output"))
      (node (ref "U$2") (pin "6") (pinfunction "I6_6") (pintype "input"))
    )
    (net (code "36") (name "Net-(IC6C-O)") (class "Default")
      (node (ref "IC6") (pin "8") (pinfunction "O_8") (pintype "output"))
      (node (ref "U$2") (pin "7") (pinfunction "I7_7") (pintype "input"))
    )
    (net (code "37") (name "Net-(IC6D-O)") (class "Default")
      (node (ref "IC6") (pin "11") (pinfunction "O_11") (pintype "output"))
      (node (ref "U$2") (pin "8") (pinfunction "I8_8") (pintype "input"))
    )
    (net (code "38") (name "Net-(IC7A-O)") (class "Default")
      (node (ref "IC7") (pin "3") (pinfunction "O_3") (pintype "output"))
      (node (ref "U$5") (pin "1") (pinfunction "I1_1") (pintype "input"))
    )
    (net (code "39") (name "Net-(IC7B-O)") (class "Default")
      (node (ref "IC7") (pin "6") (pinfunction "O_6") (pintype "output"))
      (node (ref "U$5") (pin "2") (pinfunction "I2_2") (pintype "input"))
    )
    (net (code "40") (name "Net-(IC7C-O)") (class "Default")
      (node (ref "IC7") (pin "8") (pinfunction "O_8") (pintype "output"))
      (node (ref "U$5") (pin "3") (pinfunction "I3_3") (pintype "input"))
    )
    (net (code "41") (name "Net-(IC7D-O)") (class "Default")
      (node (ref "IC7") (pin "11") (pinfunction "O_11") (pintype "output"))
      (node (ref "U$5") (pin "4") (pinfunction "I4_4") (pintype "input"))
    )
    (net (code "42") (name "Net-(IC8A-1D2)") (class "Default")
      (node (ref "IC8") (pin "2") (pinfunction "1Q1_2") (pintype "tri_state"))
      (node (ref "IC8") (pin "46") (pinfunction "1D2_46") (pintype "input"))
      (node (ref "IC9") (pin "1") (pinfunction "I0_1") (pintype "input"))
    )
    (net (code "43") (name "Net-(IC8A-1D3)") (class "Default")
      (node (ref "IC8") (pin "3") (pinfunction "1Q2_3") (pintype "tri_state"))
      (node (ref "IC8") (pin "44") (pinfunction "1D3_44") (pintype "input"))
      (node (ref "IC9") (pin "4") (pinfunction "I0_4") (pintype "input"))
    )
    (net (code "44") (name "Net-(IC8A-1D4)") (class "Default")
      (node (ref "IC8") (pin "43") (pinfunction "1D4_43") (pintype "input"))
      (node (ref "IC8") (pin "5") (pinfunction "1Q3_5") (pintype "tri_state"))
      (node (ref "IC9") (pin "9") (pinfunction "I0_9") (pintype "input"))
    )
    (net (code "45") (name "Net-(IC8A-1D5)") (class "Default")
      (node (ref "IC8") (pin "41") (pinfunction "1D5_41") (pintype "input"))
      (node (ref "IC8") (pin "6") (pinfunction "1Q4_6") (pintype "tri_state"))
      (node (ref "IC9") (pin "12") (pinfunction "I0_12") (pintype "input"))
    )
    (net (code "46") (name "Net-(IC9A-O)") (class "Default")
      (node (ref "IC9") (pin "3") (pinfunction "O_3") (pintype "output"))
      (node (ref "U$3") (pin "1") (pinfunction "I1_1") (pintype "input"))
    )
    (net (code "47") (name "Net-(IC9B-O)") (class "Default")
      (node (ref "IC9") (pin "6") (pinfunction "O_6") (pintype "output"))
      (node (ref "U$3") (pin "2") (pinfunction "I2_2") (pintype "input"))
    )
    (net (code "48") (name "Net-(IC9C-O)") (class "Default")
      (node (ref "IC9") (pin "8") (pinfunction "O_8") (pintype "output"))
      (node (ref "U$3") (pin "3") (pinfunction "I3_3") (pintype "input"))
    )
    (net (code "49") (name "Net-(IC9D-O)") (class "Default")
      (node (ref "IC9") (pin "11") (pinfunction "O_11") (pintype "output"))
      (node (ref "U$3") (pin "4") (pinfunction "I4_4") (pintype "input"))
    )
    (net (code "50") (name "Net-(IC10A-I0)") (class "Default")
      (node (ref "IC10") (pin "1") (pinfunction "I0_1") (pintype "input"))
      (node (ref "IC3") (pin "40") (pinfunction "1D6_40") (pintype "input"))
      (node (ref "IC3") (pin "8") (pinfunction "1Q5_8") (pintype "tri_state"))
    )
    (net (code "51") (name "Net-(IC10A-O)") (class "Default")
      (node (ref "IC10") (pin "3") (pinfunction "O_3") (pintype "output"))
      (node (ref "U$5") (pin "5") (pinfunction "I5_5") (pintype "input"))
    )
    (net (code "52") (name "Net-(IC10B-I0)") (class "Default")
      (node (ref "IC10") (pin "4") (pinfunction "I0_4") (pintype "input"))
      (node (ref "IC3") (pin "38") (pinfunction "1D7_38") (pintype "input"))
      (node (ref "IC3") (pin "9") (pinfunction "1Q6_9") (pintype "tri_state"))
    )
    (net (code "53") (name "Net-(IC10B-O)") (class "Default")
      (node (ref "IC10") (pin "6") (pinfunction "O_6") (pintype "output"))
      (node (ref "U$5") (pin "6") (pinfunction "I6_6") (pintype "input"))
    )
    (net (code "54") (name "Net-(IC10C-I0)") (class "Default")
      (node (ref "IC10") (pin "9") (pinfunction "I0_9") (pintype "input"))
      (node (ref "IC3") (pin "11") (pinfunction "1Q7_11") (pintype "tri_state"))
      (node (ref "IC3") (pin "37") (pinfunction "1D8_37") (pintype "input"))
    )
    (net (code "55") (name "Net-(IC10C-O)") (class "Default")
      (node (ref "IC10") (pin "8") (pinfunction "O_8") (pintype "output"))
      (node (ref "U$5") (pin "7") (pinfunction "I7_7") (pintype "input"))
    )
    (net (code "56") (name "Net-(IC10D-I0)") (class "Default")
      (node (ref "IC10") (pin "12") (pinfunction "I0_12") (pintype "input"))
      (node (ref "IC3") (pin "12") (pinfunction "1Q8_12") (pintype "tri_state"))
      (node (ref "IC3") (pin "36") (pinfunction "2D1_36") (pintype "input"))
    )
    (net (code "57") (name "Net-(IC10D-O)") (class "Default")
      (node (ref "IC10") (pin "11") (pinfunction "O_11") (pintype "output"))
      (node (ref "U$5") (pin "8") (pinfunction "I8_8") (pintype "input"))
    )
    (net (code "58") (name "Net-(IC11A-I0)") (class "Default")
      (node (ref "IC11") (pin "1") (pinfunction "I0_1") (pintype "input"))
      (node (ref "IC8") (pin "40") (pinfunction "1D6_40") (pintype "input"))
      (node (ref "IC8") (pin "8") (pinfunction "1Q5_8") (pintype "tri_state"))
    )
    (net (code "59") (name "Net-(IC11A-O)") (class "Default")
      (node (ref "IC11") (pin "3") (pinfunction "O_3") (pintype "output"))
      (node (ref "U$3") (pin "5") (pinfunction "I5_5") (pintype "input"))
    )
    (net (code "60") (name "Net-(IC11B-I0)") (class "Default")
      (node (ref "IC11") (pin "4") (pinfunction "I0_4") (pintype "input"))
      (node (ref "IC8") (pin "38") (pinfunction "1D7_38") (pintype "input"))
      (node (ref "IC8") (pin "9") (pinfunction "1Q6_9") (pintype "tri_state"))
    )
    (net (code "61") (name "Net-(IC11B-O)") (class "Default")
      (node (ref "IC11") (pin "6") (pinfunction "O_6") (pintype "output"))
      (node (ref "U$3") (pin "6") (pinfunction "I6_6") (pintype "input"))
    )
    (net (code "62") (name "Net-(IC11C-I0)") (class "Default")
      (node (ref "IC11") (pin "9") (pinfunction "I0_9") (pintype "input"))
      (node (ref "IC8") (pin "11") (pinfunction "1Q7_11") (pintype "tri_state"))
      (node (ref "IC8") (pin "37") (pinfunction "1D8_37") (pintype "input"))
    )
    (net (code "63") (name "Net-(IC11C-O)") (class "Default")
      (node (ref "IC11") (pin "8") (pinfunction "O_8") (pintype "output"))
      (node (ref "U$3") (pin "7") (pinfunction "I7_7") (pintype "input"))
    )
    (net (code "64") (name "Net-(IC11D-I0)") (class "Default")
      (node (ref "IC11") (pin "12") (pinfunction "I0_12") (pintype "input"))
      (node (ref "IC8") (pin "12") (pinfunction "1Q8_12") (pintype "tri_state"))
      (node (ref "IC8") (pin "36") (pinfunction "2D1_36") (pintype "input"))
    )
    (net (code "65") (name "Net-(IC11D-O)") (class "Default")
      (node (ref "IC11") (pin "11") (pinfunction "O_11") (pintype "output"))
      (node (ref "U$3") (pin "8") (pinfunction "I8_8") (pintype "input"))
    )
    (net (code "66") (name "Net-(IC12A-I0)") (class "Default")
      (node (ref "IC12") (pin "1") (pinfunction "I0_1") (pintype "input"))
      (node (ref "IC8") (pin "13") (pinfunction "2Q1_13") (pintype "tri_state"))
      (node (ref "IC8") (pin "35") (pinfunction "2D2_35") (pintype "input"))
    )
    (net (code "67") (name "Net-(IC12A-O)") (class "Default")
      (node (ref "IC12") (pin "3") (pinfunction "O_3") (pintype "output"))
      (node (ref "U$4") (pin "1") (pinfunction "I1_1") (pintype "input"))
    )
    (net (code "68") (name "Net-(IC12B-I0)") (class "Default")
      (node (ref "IC12") (pin "4") (pinfunction "I0_4") (pintype "input"))
      (node (ref "IC8") (pin "14") (pinfunction "2Q2_14") (pintype "tri_state"))
      (node (ref "IC8") (pin "33") (pinfunction "2D3_33") (pintype "input"))
    )
    (net (code "69") (name "Net-(IC12B-O)") (class "Default")
      (node (ref "IC12") (pin "6") (pinfunction "O_6") (pintype "output"))
      (node (ref "U$4") (pin "2") (pinfunction "I2_2") (pintype "input"))
    )
    (net (code "70") (name "Net-(IC12C-I0)") (class "Default")
      (node (ref "IC12") (pin "9") (pinfunction "I0_9") (pintype "input"))
      (node (ref "IC8") (pin "16") (pinfunction "2Q3_16") (pintype "tri_state"))
      (node (ref "IC8") (pin "32") (pinfunction "2D4_32") (pintype "input"))
    )
    (net (code "71") (name "Net-(IC12C-O)") (class "Default")
      (node (ref "IC12") (pin "8") (pinfunction "O_8") (pintype "output"))
      (node (ref "U$4") (pin "3") (pinfunction "I3_3") (pintype "input"))
    )
    (net (code "72") (name "Net-(IC12D-I0)") (class "Default")
      (node (ref "IC12") (pin "12") (pinfunction "I0_12") (pintype "input"))
      (node (ref "IC8") (pin "17") (pinfunction "2Q4_17") (pintype "tri_state"))
      (node (ref "IC8") (pin "30") (pinfunction "2D5_30") (pintype "input"))
    )
    (net (code "73") (name "Net-(IC12D-O)") (class "Default")
      (node (ref "IC12") (pin "11") (pinfunction "O_11") (pintype "output"))
      (node (ref "U$4") (pin "4") (pinfunction "I4_4") (pintype "input"))
    )
    (net (code "74") (name "Net-(IC13A-I0)") (class "Default")
      (node (ref "IC13") (pin "1") (pinfunction "I0_1") (pintype "input"))
      (node (ref "IC8") (pin "19") (pinfunction "2Q5_19") (pintype "tri_state"))
      (node (ref "IC8") (pin "29") (pinfunction "2D6_29") (pintype "input"))
    )
    (net (code "75") (name "Net-(IC13A-O)") (class "Default")
      (node (ref "IC13") (pin "3") (pinfunction "O_3") (pintype "output"))
      (node (ref "U$4") (pin "5") (pinfunction "I5_5") (pintype "input"))
    )
    (net (code "76") (name "Net-(IC13B-I0)") (class "Default")
      (node (ref "IC13") (pin "4") (pinfunction "I0_4") (pintype "input"))
      (node (ref "IC8") (pin "20") (pinfunction "2Q6_20") (pintype "tri_state"))
      (node (ref "IC8") (pin "27") (pinfunction "2D7_27") (pintype "input"))
    )
    (net (code "77") (name "Net-(IC13B-O)") (class "Default")
      (node (ref "IC13") (pin "6") (pinfunction "O_6") (pintype "output"))
      (node (ref "U$4") (pin "6") (pinfunction "I6_6") (pintype "input"))
    )
    (net (code "78") (name "Net-(IC13C-I0)") (class "Default")
      (node (ref "IC13") (pin "9") (pinfunction "I0_9") (pintype "input"))
      (node (ref "IC8") (pin "22") (pinfunction "2Q7_22") (pintype "tri_state"))
      (node (ref "IC8") (pin "26") (pinfunction "2D8_26") (pintype "input"))
    )
    (net (code "79") (name "Net-(IC13C-O)") (class "Default")
      (node (ref "IC13") (pin "8") (pinfunction "O_8") (pintype "output"))
      (node (ref "U$4") (pin "7") (pinfunction "I7_7") (pintype "input"))
    )
    (net (code "80") (name "Net-(IC13D-I0)") (class "Default")
      (node (ref "IC13") (pin "12") (pinfunction "I0_12") (pintype "input"))
      (node (ref "IC8") (pin "23") (pinfunction "2Q8_23") (pintype "tri_state"))
      (node (ref "X11") (pin "1") (pinfunction "S_1") (pintype "passive"))
    )
    (net (code "81") (name "Net-(IC13D-O)") (class "Default")
      (node (ref "IC13") (pin "11") (pinfunction "O_11") (pintype "output"))
      (node (ref "U$4") (pin "8") (pinfunction "I8_8") (pintype "input"))
    )
    (net (code "82") (name "Net-(IC14A-I0)") (class "Default")
      (node (ref "IC14") (pin "1") (pinfunction "I0_1") (pintype "input"))
      (node (ref "IC3") (pin "13") (pinfunction "2Q1_13") (pintype "tri_state"))
      (node (ref "IC3") (pin "35") (pinfunction "2D2_35") (pintype "input"))
    )
    (net (code "83") (name "Net-(IC14A-O)") (class "Default")
      (node (ref "IC14") (pin "3") (pinfunction "O_3") (pintype "output"))
      (node (ref "U$6") (pin "1") (pinfunction "I1_1") (pintype "input"))
    )
    (net (code "84") (name "Net-(IC14B-I0)") (class "Default")
      (node (ref "IC14") (pin "4") (pinfunction "I0_4") (pintype "input"))
      (node (ref "IC3") (pin "14") (pinfunction "2Q2_14") (pintype "tri_state"))
      (node (ref "IC3") (pin "33") (pinfunction "2D3_33") (pintype "input"))
    )
    (net (code "85") (name "Net-(IC14B-O)") (class "Default")
      (node (ref "IC14") (pin "6") (pinfunction "O_6") (pintype "output"))
      (node (ref "U$6") (pin "2") (pinfunction "I2_2") (pintype "input"))
    )
    (net (code "86") (name "Net-(IC14C-I0)") (class "Default")
      (node (ref "IC14") (pin "9") (pinfunction "I0_9") (pintype "input"))
      (node (ref "IC3") (pin "16") (pinfunction "2Q3_16") (pintype "tri_state"))
      (node (ref "IC3") (pin "32") (pinfunction "2D4_32") (pintype "input"))
    )
    (net (code "87") (name "Net-(IC14C-O)") (class "Default")
      (node (ref "IC14") (pin "8") (pinfunction "O_8") (pintype "output"))
      (node (ref "U$6") (pin "3") (pinfunction "I3_3") (pintype "input"))
    )
    (net (code "88") (name "Net-(IC14D-I0)") (class "Default")
      (node (ref "IC14") (pin "12") (pinfunction "I0_12") (pintype "input"))
      (node (ref "IC3") (pin "17") (pinfunction "2Q4_17") (pintype "tri_state"))
      (node (ref "IC3") (pin "30") (pinfunction "2D5_30") (pintype "input"))
    )
    (net (code "89") (name "Net-(IC14D-O)") (class "Default")
      (node (ref "IC14") (pin "11") (pinfunction "O_11") (pintype "output"))
      (node (ref "U$6") (pin "4") (pinfunction "I4_4") (pintype "input"))
    )
    (net (code "90") (name "Net-(IC15A-I0)") (class "Default")
      (node (ref "IC15") (pin "1") (pinfunction "I0_1") (pintype "input"))
      (node (ref "IC3") (pin "19") (pinfunction "2Q5_19") (pintype "tri_state"))
      (node (ref "IC3") (pin "29") (pinfunction "2D6_29") (pintype "input"))
    )
    (net (code "91") (name "Net-(IC15A-O)") (class "Default")
      (node (ref "IC15") (pin "3") (pinfunction "O_3") (pintype "output"))
      (node (ref "U$6") (pin "5") (pinfunction "I5_5") (pintype "input"))
    )
    (net (code "92") (name "Net-(IC15B-I0)") (class "Default")
      (node (ref "IC15") (pin "4") (pinfunction "I0_4") (pintype "input"))
      (node (ref "IC3") (pin "20") (pinfunction "2Q6_20") (pintype "tri_state"))
      (node (ref "IC3") (pin "27") (pinfunction "2D7_27") (pintype "input"))
    )
    (net (code "93") (name "Net-(IC15B-O)") (class "Default")
      (node (ref "IC15") (pin "6") (pinfunction "O_6") (pintype "output"))
      (node (ref "U$6") (pin "6") (pinfunction "I6_6") (pintype "input"))
    )
    (net (code "94") (name "Net-(IC15C-I0)") (class "Default")
      (node (ref "IC15") (pin "9") (pinfunction "I0_9") (pintype "input"))
      (node (ref "IC3") (pin "22") (pinfunction "2Q7_22") (pintype "tri_state"))
      (node (ref "IC3") (pin "26") (pinfunction "2D8_26") (pintype "input"))
    )
    (net (code "95") (name "Net-(IC15C-O)") (class "Default")
      (node (ref "IC15") (pin "8") (pinfunction "O_8") (pintype "output"))
      (node (ref "U$6") (pin "7") (pinfunction "I7_7") (pintype "input"))
    )
    (net (code "96") (name "Net-(IC15D-I0)") (class "Default")
      (node (ref "IC15") (pin "12") (pinfunction "I0_12") (pintype "input"))
      (node (ref "IC16") (pin "47") (pinfunction "1D1_47") (pintype "input"))
      (node (ref "IC3") (pin "23") (pinfunction "2Q8_23") (pintype "tri_state"))
    )
    (net (code "97") (name "Net-(IC15D-O)") (class "Default")
      (node (ref "IC15") (pin "11") (pinfunction "O_11") (pintype "output"))
      (node (ref "U$6") (pin "8") (pinfunction "I8_8") (pintype "input"))
    )
    (net (code "98") (name "Net-(IC16A-1CLK)") (class "Default")
      (node (ref "IC1") (pin "25") (pinfunction "2CLK_25") (pintype "input"))
      (node (ref "IC1") (pin "48") (pinfunction "1CLK_48") (pintype "input"))
      (node (ref "IC16") (pin "25") (pinfunction "2CLK_25") (pintype "input"))
      (node (ref "IC16") (pin "48") (pinfunction "1CLK_48") (pintype "input"))
      (node (ref "IC21") (pin "25") (pinfunction "2CLK_25") (pintype "input"))
      (node (ref "IC21") (pin "48") (pinfunction "1CLK_48") (pintype "input"))
      (node (ref "IC26") (pin "25") (pinfunction "2CLK_25") (pintype "input"))
      (node (ref "IC26") (pin "48") (pinfunction "1CLK_48") (pintype "input"))
      (node (ref "IC3") (pin "25") (pinfunction "2CLK_25") (pintype "input"))
      (node (ref "IC3") (pin "48") (pinfunction "1CLK_48") (pintype "input"))
      (node (ref "IC8") (pin "25") (pinfunction "2CLK_25") (pintype "input"))
      (node (ref "IC8") (pin "48") (pinfunction "1CLK_48") (pintype "input"))
      (node (ref "X11") (pin "5") (pinfunction "S_5") (pintype "passive"))
    )
    (net (code "99") (name "Net-(IC16A-1D2)") (class "Default")
      (node (ref "IC16") (pin "2") (pinfunction "1Q1_2") (pintype "tri_state"))
      (node (ref "IC16") (pin "46") (pinfunction "1D2_46") (pintype "input"))
      (node (ref "IC17") (pin "1") (pinfunction "I0_1") (pintype "input"))
    )
    (net (code "100") (name "Net-(IC16A-1D3)") (class "Default")
      (node (ref "IC16") (pin "3") (pinfunction "1Q2_3") (pintype "tri_state"))
      (node (ref "IC16") (pin "44") (pinfunction "1D3_44") (pintype "input"))
      (node (ref "IC17") (pin "4") (pinfunction "I0_4") (pintype "input"))
    )
    (net (code "101") (name "Net-(IC16A-1D4)") (class "Default")
      (node (ref "IC16") (pin "43") (pinfunction "1D4_43") (pintype "input"))
      (node (ref "IC16") (pin "5") (pinfunction "1Q3_5") (pintype "tri_state"))
      (node (ref "IC17") (pin "9") (pinfunction "I0_9") (pintype "input"))
    )
    (net (code "102") (name "Net-(IC16A-1D5)") (class "Default")
      (node (ref "IC16") (pin "41") (pinfunction "1D5_41") (pintype "input"))
      (node (ref "IC16") (pin "6") (pinfunction "1Q4_6") (pintype "tri_state"))
      (node (ref "IC17") (pin "12") (pinfunction "I0_12") (pintype "input"))
    )
    (net (code "103") (name "Net-(IC16A-1D6)") (class "Default")
      (node (ref "IC16") (pin "40") (pinfunction "1D6_40") (pintype "input"))
      (node (ref "IC16") (pin "8") (pinfunction "1Q5_8") (pintype "tri_state"))
      (node (ref "IC18") (pin "1") (pinfunction "I0_1") (pintype "input"))
    )
    (net (code "104") (name "Net-(IC16A-1D7)") (class "Default")
      (node (ref "IC16") (pin "38") (pinfunction "1D7_38") (pintype "input"))
      (node (ref "IC16") (pin "9") (pinfunction "1Q6_9") (pintype "tri_state"))
      (node (ref "IC18") (pin "4") (pinfunction "I0_4") (pintype "input"))
    )
    (net (code "105") (name "Net-(IC16A-1D8)") (class "Default")
      (node (ref "IC16") (pin "11") (pinfunction "1Q7_11") (pintype "tri_state"))
      (node (ref "IC16") (pin "37") (pinfunction "1D8_37") (pintype "input"))
      (node (ref "IC18") (pin "9") (pinfunction "I0_9") (pintype "input"))
    )
    (net (code "106") (name "Net-(IC16A-1Q8)") (class "Default")
      (node (ref "IC16") (pin "12") (pinfunction "1Q8_12") (pintype "tri_state"))
      (node (ref "IC16") (pin "36") (pinfunction "2D1_36") (pintype "input"))
      (node (ref "IC18") (pin "12") (pinfunction "I0_12") (pintype "input"))
    )
    (net (code "107") (name "Net-(IC16A-2D2)") (class "Default")
      (node (ref "IC16") (pin "13") (pinfunction "2Q1_13") (pintype "tri_state"))
      (node (ref "IC16") (pin "35") (pinfunction "2D2_35") (pintype "input"))
      (node (ref "IC19") (pin "1") (pinfunction "I0_1") (pintype "input"))
    )
    (net (code "108") (name "Net-(IC16A-2D3)") (class "Default")
      (node (ref "IC16") (pin "14") (pinfunction "2Q2_14") (pintype "tri_state"))
      (node (ref "IC16") (pin "33") (pinfunction "2D3_33") (pintype "input"))
      (node (ref "IC19") (pin "4") (pinfunction "I0_4") (pintype "input"))
    )
    (net (code "109") (name "Net-(IC16A-2D4)") (class "Default")
      (node (ref "IC16") (pin "16") (pinfunction "2Q3_16") (pintype "tri_state"))
      (node (ref "IC16") (pin "32") (pinfunction "2D4_32") (pintype "input"))
      (node (ref "IC19") (pin "9") (pinfunction "I0_9") (pintype "input"))
    )
    (net (code "110") (name "Net-(IC16A-2D5)") (class "Default")
      (node (ref "IC16") (pin "17") (pinfunction "2Q4_17") (pintype "tri_state"))
      (node (ref "IC16") (pin "30") (pinfunction "2D5_30") (pintype "input"))
      (node (ref "IC19") (pin "12") (pinfunction "I0_12") (pintype "input"))
    )
    (net (code "111") (name "Net-(IC16A-2D6)") (class "Default")
      (node (ref "IC16") (pin "19") (pinfunction "2Q5_19") (pintype "tri_state"))
      (node (ref "IC16") (pin "29") (pinfunction "2D6_29") (pintype "input"))
      (node (ref "IC20") (pin "1") (pinfunction "I0_1") (pintype "input"))
    )
    (net (code "112") (name "Net-(IC16A-2D7)") (class "Default")
      (node (ref "IC16") (pin "20") (pinfunction "2Q6_20") (pintype "tri_state"))
      (node (ref "IC16") (pin "27") (pinfunction "2D7_27") (pintype "input"))
      (node (ref "IC20") (pin "4") (pinfunction "I0_4") (pintype "input"))
    )
    (net (code "113") (name "Net-(IC16A-2D8)") (class "Default")
      (node (ref "IC16") (pin "22") (pinfunction "2Q7_22") (pintype "tri_state"))
      (node (ref "IC16") (pin "26") (pinfunction "2D8_26") (pintype "input"))
      (node (ref "IC20") (pin "9") (pinfunction "I0_9") (pintype "input"))
    )
    (net (code "114") (name "Net-(IC16A-2Q8)") (class "Default")
      (node (ref "IC1") (pin "47") (pinfunction "1D1_47") (pintype "input"))
      (node (ref "IC16") (pin "23") (pinfunction "2Q8_23") (pintype "tri_state"))
      (node (ref "IC20") (pin "12") (pinfunction "I0_12") (pintype "input"))
    )
    (net (code "115") (name "Net-(IC17A-O)") (class "Default")
      (node (ref "IC17") (pin "3") (pinfunction "O_3") (pintype "output"))
      (node (ref "U$7") (pin "1") (pinfunction "I1_1") (pintype "input"))
    )
    (net (code "116") (name "Net-(IC17B-O)") (class "Default")
      (node (ref "IC17") (pin "6") (pinfunction "O_6") (pintype "output"))
      (node (ref "U$7") (pin "2") (pinfunction "I2_2") (pintype "input"))
    )
    (net (code "117") (name "Net-(IC17C-O)") (class "Default")
      (node (ref "IC17") (pin "8") (pinfunction "O_8") (pintype "output"))
      (node (ref "U$7") (pin "3") (pinfunction "I3_3") (pintype "input"))
    )
    (net (code "118") (name "Net-(IC17D-O)") (class "Default")
      (node (ref "IC17") (pin "11") (pinfunction "O_11") (pintype "output"))
      (node (ref "U$7") (pin "4") (pinfunction "I4_4") (pintype "input"))
    )
    (net (code "119") (name "Net-(IC18A-O)") (class "Default")
      (node (ref "IC18") (pin "3") (pinfunction "O_3") (pintype "output"))
      (node (ref "U$7") (pin "5") (pinfunction "I5_5") (pintype "input"))
    )
    (net (code "120") (name "Net-(IC18B-O)") (class "Default")
      (node (ref "IC18") (pin "6") (pinfunction "O_6") (pintype "output"))
      (node (ref "U$7") (pin "6") (pinfunction "I6_6") (pintype "input"))
    )
    (net (code "121") (name "Net-(IC18C-O)") (class "Default")
      (node (ref "IC18") (pin "8") (pinfunction "O_8") (pintype "output"))
      (node (ref "U$7") (pin "7") (pinfunction "I7_7") (pintype "input"))
    )
    (net (code "122") (name "Net-(IC18D-O)") (class "Default")
      (node (ref "IC18") (pin "11") (pinfunction "O_11") (pintype "output"))
      (node (ref "U$7") (pin "8") (pinfunction "I8_8") (pintype "input"))
    )
    (net (code "123") (name "Net-(IC19A-O)") (class "Default")
      (node (ref "IC19") (pin "3") (pinfunction "O_3") (pintype "output"))
      (node (ref "U$8") (pin "1") (pinfunction "I1_1") (pintype "input"))
    )
    (net (code "124") (name "Net-(IC19B-O)") (class "Default")
      (node (ref "IC19") (pin "6") (pinfunction "O_6") (pintype "output"))
      (node (ref "U$8") (pin "2") (pinfunction "I2_2") (pintype "input"))
    )
    (net (code "125") (name "Net-(IC19C-O)") (class "Default")
      (node (ref "IC19") (pin "8") (pinfunction "O_8") (pintype "output"))
      (node (ref "U$8") (pin "3") (pinfunction "I3_3") (pintype "input"))
    )
    (net (code "126") (name "Net-(IC19D-O)") (class "Default")
      (node (ref "IC19") (pin "11") (pinfunction "O_11") (pintype "output"))
      (node (ref "U$8") (pin "4") (pinfunction "I4_4") (pintype "input"))
    )
    (net (code "127") (name "Net-(IC20A-O)") (class "Default")
      (node (ref "IC20") (pin "3") (pinfunction "O_3") (pintype "output"))
      (node (ref "U$8") (pin "5") (pinfunction "I5_5") (pintype "input"))
    )
    (net (code "128") (name "Net-(IC20B-O)") (class "Default")
      (node (ref "IC20") (pin "6") (pinfunction "O_6") (pintype "output"))
      (node (ref "U$8") (pin "6") (pinfunction "I6_6") (pintype "input"))
    )
    (net (code "129") (name "Net-(IC20C-O)") (class "Default")
      (node (ref "IC20") (pin "8") (pinfunction "O_8") (pintype "output"))
      (node (ref "U$8") (pin "7") (pinfunction "I7_7") (pintype "input"))
    )
    (net (code "130") (name "Net-(IC20D-O)") (class "Default")
      (node (ref "IC20") (pin "11") (pinfunction "O_11") (pintype "output"))
      (node (ref "U$8") (pin "8") (pinfunction "I8_8") (pintype "input"))
    )
    (net (code "131") (name "Net-(IC21A-1D1)") (class "Default")
      (node (ref "IC21") (pin "47") (pinfunction "1D1_47") (pintype "input"))
      (node (ref "X11") (pin "4") (pinfunction "S_4") (pintype "passive"))
    )
    (net (code "132") (name "Net-(IC21A-1D2)") (class "Default")
      (node (ref "IC21") (pin "2") (pinfunction "1Q1_2") (pintype "tri_state"))
      (node (ref "IC21") (pin "46") (pinfunction "1D2_46") (pintype "input"))
      (node (ref "IC22") (pin "1") (pinfunction "I0_1") (pintype "input"))
    )
    (net (code "133") (name "Net-(IC21A-1D3)") (class "Default")
      (node (ref "IC21") (pin "3") (pinfunction "1Q2_3") (pintype "tri_state"))
      (node (ref "IC21") (pin "44") (pinfunction "1D3_44") (pintype "input"))
      (node (ref "IC22") (pin "4") (pinfunction "I0_4") (pintype "input"))
    )
    (net (code "134") (name "Net-(IC21A-1D4)") (class "Default")
      (node (ref "IC21") (pin "43") (pinfunction "1D4_43") (pintype "input"))
      (node (ref "IC21") (pin "5") (pinfunction "1Q3_5") (pintype "tri_state"))
      (node (ref "IC22") (pin "9") (pinfunction "I0_9") (pintype "input"))
    )
    (net (code "135") (name "Net-(IC21A-1D5)") (class "Default")
      (node (ref "IC21") (pin "41") (pinfunction "1D5_41") (pintype "input"))
      (node (ref "IC21") (pin "6") (pinfunction "1Q4_6") (pintype "tri_state"))
      (node (ref "IC22") (pin "12") (pinfunction "I0_12") (pintype "input"))
    )
    (net (code "136") (name "Net-(IC21A-1D6)") (class "Default")
      (node (ref "IC21") (pin "40") (pinfunction "1D6_40") (pintype "input"))
      (node (ref "IC21") (pin "8") (pinfunction "1Q5_8") (pintype "tri_state"))
      (node (ref "IC23") (pin "1") (pinfunction "I0_1") (pintype "input"))
    )
    (net (code "137") (name "Net-(IC21A-1D7)") (class "Default")
      (node (ref "IC21") (pin "38") (pinfunction "1D7_38") (pintype "input"))
      (node (ref "IC21") (pin "9") (pinfunction "1Q6_9") (pintype "tri_state"))
      (node (ref "IC23") (pin "4") (pinfunction "I0_4") (pintype "input"))
    )
    (net (code "138") (name "Net-(IC21A-1D8)") (class "Default")
      (node (ref "IC21") (pin "11") (pinfunction "1Q7_11") (pintype "tri_state"))
      (node (ref "IC21") (pin "37") (pinfunction "1D8_37") (pintype "input"))
      (node (ref "IC23") (pin "9") (pinfunction "I0_9") (pintype "input"))
    )
    (net (code "139") (name "Net-(IC21A-1Q8)") (class "Default")
      (node (ref "IC21") (pin "12") (pinfunction "1Q8_12") (pintype "tri_state"))
      (node (ref "IC21") (pin "36") (pinfunction "2D1_36") (pintype "input"))
      (node (ref "IC23") (pin "12") (pinfunction "I0_12") (pintype "input"))
    )
    (net (code "140") (name "Net-(IC21A-2D2)") (class "Default")
      (node (ref "IC21") (pin "13") (pinfunction "2Q1_13") (pintype "tri_state"))
      (node (ref "IC21") (pin "35") (pinfunction "2D2_35") (pintype "input"))
      (node (ref "IC24") (pin "1") (pinfunction "I0_1") (pintype "input"))
    )
    (net (code "141") (name "Net-(IC21A-2D3)") (class "Default")
      (node (ref "IC21") (pin "14") (pinfunction "2Q2_14") (pintype "tri_state"))
      (node (ref "IC21") (pin "33") (pinfunction "2D3_33") (pintype "input"))
      (node (ref "IC24") (pin "4") (pinfunction "I0_4") (pintype "input"))
    )
    (net (code "142") (name "Net-(IC21A-2D4)") (class "Default")
      (node (ref "IC21") (pin "16") (pinfunction "2Q3_16") (pintype "tri_state"))
      (node (ref "IC21") (pin "32") (pinfunction "2D4_32") (pintype "input"))
      (node (ref "IC24") (pin "9") (pinfunction "I0_9") (pintype "input"))
    )
    (net (code "143") (name "Net-(IC21A-2D5)") (class "Default")
      (node (ref "IC21") (pin "17") (pinfunction "2Q4_17") (pintype "tri_state"))
      (node (ref "IC21") (pin "30") (pinfunction "2D5_30") (pintype "input"))
      (node (ref "IC24") (pin "12") (pinfunction "I0_12") (pintype "input"))
    )
    (net (code "144") (name "Net-(IC21A-2D6)") (class "Default")
      (node (ref "IC21") (pin "19") (pinfunction "2Q5_19") (pintype "tri_state"))
      (node (ref "IC21") (pin "29") (pinfunction "2D6_29") (pintype "input"))
      (node (ref "IC25") (pin "1") (pinfunction "I0_1") (pintype "input"))
    )
    (net (code "145") (name "Net-(IC21A-2D7)") (class "Default")
      (node (ref "IC21") (pin "20") (pinfunction "2Q6_20") (pintype "tri_state"))
      (node (ref "IC21") (pin "27") (pinfunction "2D7_27") (pintype "input"))
      (node (ref "IC25") (pin "4") (pinfunction "I0_4") (pintype "input"))
    )
    (net (code "146") (name "Net-(IC21A-2D8)") (class "Default")
      (node (ref "IC21") (pin "22") (pinfunction "2Q7_22") (pintype "tri_state"))
      (node (ref "IC21") (pin "26") (pinfunction "2D8_26") (pintype "input"))
      (node (ref "IC25") (pin "9") (pinfunction "I0_9") (pintype "input"))
    )
    (net (code "147") (name "Net-(IC21A-2Q8)") (class "Default")
      (node (ref "IC21") (pin "23") (pinfunction "2Q8_23") (pintype "tri_state"))
      (node (ref "IC25") (pin "12") (pinfunction "I0_12") (pintype "input"))
      (node (ref "IC26") (pin "47") (pinfunction "1D1_47") (pintype "input"))
    )
    (net (code "148") (name "Net-(IC22A-O)") (class "Default")
      (node (ref "IC22") (pin "3") (pinfunction "O_3") (pintype "output"))
      (node (ref "U$9") (pin "1") (pinfunction "I1_1") (pintype "input"))
    )
    (net (code "149") (name "Net-(IC22B-O)") (class "Default")
      (node (ref "IC22") (pin "6") (pinfunction "O_6") (pintype "output"))
      (node (ref "U$9") (pin "2") (pinfunction "I2_2") (pintype "input"))
    )
    (net (code "150") (name "Net-(IC22C-O)") (class "Default")
      (node (ref "IC22") (pin "8") (pinfunction "O_8") (pintype "output"))
      (node (ref "U$9") (pin "3") (pinfunction "I3_3") (pintype "input"))
    )
    (net (code "151") (name "Net-(IC22D-O)") (class "Default")
      (node (ref "IC22") (pin "11") (pinfunction "O_11") (pintype "output"))
      (node (ref "U$9") (pin "4") (pinfunction "I4_4") (pintype "input"))
    )
    (net (code "152") (name "Net-(IC23A-O)") (class "Default")
      (node (ref "IC23") (pin "3") (pinfunction "O_3") (pintype "output"))
      (node (ref "U$9") (pin "5") (pinfunction "I5_5") (pintype "input"))
    )
    (net (code "153") (name "Net-(IC23B-O)") (class "Default")
      (node (ref "IC23") (pin "6") (pinfunction "O_6") (pintype "output"))
      (node (ref "U$9") (pin "6") (pinfunction "I6_6") (pintype "input"))
    )
    (net (code "154") (name "Net-(IC23C-O)") (class "Default")
      (node (ref "IC23") (pin "8") (pinfunction "O_8") (pintype "output"))
      (node (ref "U$9") (pin "7") (pinfunction "I7_7") (pintype "input"))
    )
    (net (code "155") (name "Net-(IC23D-O)") (class "Default")
      (node (ref "IC23") (pin "11") (pinfunction "O_11") (pintype "output"))
      (node (ref "U$9") (pin "8") (pinfunction "I8_8") (pintype "input"))
    )
    (net (code "156") (name "Net-(IC24A-O)") (class "Default")
      (node (ref "IC24") (pin "3") (pinfunction "O_3") (pintype "output"))
      (node (ref "U$10") (pin "1") (pinfunction "I1_1") (pintype "input"))
    )
    (net (code "157") (name "Net-(IC24B-O)") (class "Default")
      (node (ref "IC24") (pin "6") (pinfunction "O_6") (pintype "output"))
      (node (ref "U$10") (pin "2") (pinfunction "I2_2") (pintype "input"))
    )
    (net (code "158") (name "Net-(IC24C-O)") (class "Default")
      (node (ref "IC24") (pin "8") (pinfunction "O_8") (pintype "output"))
      (node (ref "U$10") (pin "3") (pinfunction "I3_3") (pintype "input"))
    )
    (net (code "159") (name "Net-(IC24D-O)") (class "Default")
      (node (ref "IC24") (pin "11") (pinfunction "O_11") (pintype "output"))
      (node (ref "U$10") (pin "4") (pinfunction "I4_4") (pintype "input"))
    )
    (net (code "160") (name "Net-(IC25A-O)") (class "Default")
      (node (ref "IC25") (pin "3") (pinfunction "O_3") (pintype "output"))
      (node (ref "U$10") (pin "5") (pinfunction "I5_5") (pintype "input"))
    )
    (net (code "161") (name "Net-(IC25B-O)") (class "Default")
      (node (ref "IC25") (pin "6") (pinfunction "O_6") (pintype "output"))
      (node (ref "U$10") (pin "6") (pinfunction "I6_6") (pintype "input"))
    )
    (net (code "162") (name "Net-(IC25C-O)") (class "Default")
      (node (ref "IC25") (pin "8") (pinfunction "O_8") (pintype "output"))
      (node (ref "U$10") (pin "7") (pinfunction "I7_7") (pintype "input"))
    )
    (net (code "163") (name "Net-(IC25D-O)") (class "Default")
      (node (ref "IC25") (pin "11") (pinfunction "O_11") (pintype "output"))
      (node (ref "U$10") (pin "8") (pinfunction "I8_8") (pintype "input"))
    )
    (net (code "164") (name "Net-(IC26A-1D2)") (class "Default")
      (node (ref "IC26") (pin "2") (pinfunction "1Q1_2") (pintype "tri_state"))
      (node (ref "IC26") (pin "46") (pinfunction "1D2_46") (pintype "input"))
      (node (ref "IC27") (pin "1") (pinfunction "I0_1") (pintype "input"))
    )
    (net (code "165") (name "Net-(IC26A-1D3)") (class "Default")
      (node (ref "IC26") (pin "3") (pinfunction "1Q2_3") (pintype "tri_state"))
      (node (ref "IC26") (pin "44") (pinfunction "1D3_44") (pintype "input"))
      (node (ref "IC27") (pin "4") (pinfunction "I0_4") (pintype "input"))
    )
    (net (code "166") (name "Net-(IC26A-1D4)") (class "Default")
      (node (ref "IC26") (pin "43") (pinfunction "1D4_43") (pintype "input"))
      (node (ref "IC26") (pin "5") (pinfunction "1Q3_5") (pintype "tri_state"))
      (node (ref "IC27") (pin "9") (pinfunction "I0_9") (pintype "input"))
    )
    (net (code "167") (name "Net-(IC26A-1D5)") (class "Default")
      (node (ref "IC26") (pin "41") (pinfunction "1D5_41") (pintype "input"))
      (node (ref "IC26") (pin "6") (pinfunction "1Q4_6") (pintype "tri_state"))
      (node (ref "IC27") (pin "12") (pinfunction "I0_12") (pintype "input"))
    )
    (net (code "168") (name "Net-(IC26A-1D6)") (class "Default")
      (node (ref "IC26") (pin "40") (pinfunction "1D6_40") (pintype "input"))
      (node (ref "IC26") (pin "8") (pinfunction "1Q5_8") (pintype "tri_state"))
      (node (ref "IC28") (pin "1") (pinfunction "I0_1") (pintype "input"))
    )
    (net (code "169") (name "Net-(IC26A-1D7)") (class "Default")
      (node (ref "IC26") (pin "38") (pinfunction "1D7_38") (pintype "input"))
      (node (ref "IC26") (pin "9") (pinfunction "1Q6_9") (pintype "tri_state"))
      (node (ref "IC28") (pin "4") (pinfunction "I0_4") (pintype "input"))
    )
    (net (code "170") (name "Net-(IC26A-1D8)") (class "Default")
      (node (ref "IC26") (pin "11") (pinfunction "1Q7_11") (pintype "tri_state"))
      (node (ref "IC26") (pin "37") (pinfunction "1D8_37") (pintype "input"))
      (node (ref "IC28") (pin "9") (pinfunction "I0_9") (pintype "input"))
    )
    (net (code "171") (name "Net-(IC26A-1Q8)") (class "Default")
      (node (ref "IC26") (pin "12") (pinfunction "1Q8_12") (pintype "tri_state"))
      (node (ref "IC26") (pin "36") (pinfunction "2D1_36") (pintype "input"))
      (node (ref "IC28") (pin "12") (pinfunction "I0_12") (pintype "input"))
    )
    (net (code "172") (name "Net-(IC26A-2D2)") (class "Default")
      (node (ref "IC26") (pin "13") (pinfunction "2Q1_13") (pintype "tri_state"))
      (node (ref "IC26") (pin "35") (pinfunction "2D2_35") (pintype "input"))
      (node (ref "IC29") (pin "1") (pinfunction "I0_1") (pintype "input"))
    )
    (net (code "173") (name "Net-(IC26A-2D3)") (class "Default")
      (node (ref "IC26") (pin "14") (pinfunction "2Q2_14") (pintype "tri_state"))
      (node (ref "IC26") (pin "33") (pinfunction "2D3_33") (pintype "input"))
      (node (ref "IC29") (pin "4") (pinfunction "I0_4") (pintype "input"))
    )
    (net (code "174") (name "Net-(IC26A-2D4)") (class "Default")
      (node (ref "IC26") (pin "16") (pinfunction "2Q3_16") (pintype "tri_state"))
      (node (ref "IC26") (pin "32") (pinfunction "2D4_32") (pintype "input"))
      (node (ref "IC29") (pin "9") (pinfunction "I0_9") (pintype "input"))
    )
    (net (code "175") (name "Net-(IC26A-2D5)") (class "Default")
      (node (ref "IC26") (pin "17") (pinfunction "2Q4_17") (pintype "tri_state"))
      (node (ref "IC26") (pin "30") (pinfunction "2D5_30") (pintype "input"))
      (node (ref "IC29") (pin "12") (pinfunction "I0_12") (pintype "input"))
    )
    (net (code "176") (name "Net-(IC26A-2D6)") (class "Default")
      (node (ref "IC26") (pin "19") (pinfunction "2Q5_19") (pintype "tri_state"))
      (node (ref "IC26") (pin "29") (pinfunction "2D6_29") (pintype "input"))
      (node (ref "IC30") (pin "1") (pinfunction "I0_1") (pintype "input"))
    )
    (net (code "177") (name "Net-(IC26A-2D7)") (class "Default")
      (node (ref "IC26") (pin "20") (pinfunction "2Q6_20") (pintype "tri_state"))
      (node (ref "IC26") (pin "27") (pinfunction "2D7_27") (pintype "input"))
      (node (ref "IC30") (pin "4") (pinfunction "I0_4") (pintype "input"))
    )
    (net (code "178") (name "Net-(IC26A-2D8)") (class "Default")
      (node (ref "IC26") (pin "22") (pinfunction "2Q7_22") (pintype "tri_state"))
      (node (ref "IC26") (pin "26") (pinfunction "2D8_26") (pintype "input"))
      (node (ref "IC30") (pin "9") (pinfunction "I0_9") (pintype "input"))
    )
    (net (code "179") (name "Net-(IC26A-2Q8)") (class "Default")
      (node (ref "IC26") (pin "23") (pinfunction "2Q8_23") (pintype "tri_state"))
      (node (ref "IC3") (pin "47") (pinfunction "1D1_47") (pintype "input"))
      (node (ref "IC30") (pin "12") (pinfunction "I0_12") (pintype "input"))
    )
    (net (code "180") (name "Net-(IC27A-O)") (class "Default")
      (node (ref "IC27") (pin "3") (pinfunction "O_3") (pintype "output"))
      (node (ref "U$11") (pin "1") (pinfunction "I1_1") (pintype "input"))
    )
    (net (code "181") (name "Net-(IC27B-O)") (class "Default")
      (node (ref "IC27") (pin "6") (pinfunction "O_6") (pintype "output"))
      (node (ref "U$11") (pin "2") (pinfunction "I2_2") (pintype "input"))
    )
    (net (code "182") (name "Net-(IC27C-O)") (class "Default")
      (node (ref "IC27") (pin "8") (pinfunction "O_8") (pintype "output"))
      (node (ref "U$11") (pin "3") (pinfunction "I3_3") (pintype "input"))
    )
    (net (code "183") (name "Net-(IC27D-O)") (class "Default")
      (node (ref "IC27") (pin "11") (pinfunction "O_11") (pintype "output"))
      (node (ref "U$11") (pin "4") (pinfunction "I4_4") (pintype "input"))
    )
    (net (code "184") (name "Net-(IC28A-O)") (class "Default")
      (node (ref "IC28") (pin "3") (pinfunction "O_3") (pintype "output"))
      (node (ref "U$11") (pin "5") (pinfunction "I5_5") (pintype "input"))
    )
    (net (code "185") (name "Net-(IC28B-O)") (class "Default")
      (node (ref "IC28") (pin "6") (pinfunction "O_6") (pintype "output"))
      (node (ref "U$11") (pin "6") (pinfunction "I6_6") (pintype "input"))
    )
    (net (code "186") (name "Net-(IC28C-O)") (class "Default")
      (node (ref "IC28") (pin "8") (pinfunction "O_8") (pintype "output"))
      (node (ref "U$11") (pin "7") (pinfunction "I7_7") (pintype "input"))
    )
    (net (code "187") (name "Net-(IC28D-O)") (class "Default")
      (node (ref "IC28") (pin "11") (pinfunction "O_11") (pintype "output"))
      (node (ref "U$11") (pin "8") (pinfunction "I8_8") (pintype "input"))
    )
    (net (code "188") (name "Net-(IC29A-O)") (class "Default")
      (node (ref "IC29") (pin "3") (pinfunction "O_3") (pintype "output"))
      (node (ref "U$12") (pin "1") (pinfunction "I1_1") (pintype "input"))
    )
    (net (code "189") (name "Net-(IC29B-O)") (class "Default")
      (node (ref "IC29") (pin "6") (pinfunction "O_6") (pintype "output"))
      (node (ref "U$12") (pin "2") (pinfunction "I2_2") (pintype "input"))
    )
    (net (code "190") (name "Net-(IC29C-O)") (class "Default")
      (node (ref "IC29") (pin "8") (pinfunction "O_8") (pintype "output"))
      (node (ref "U$12") (pin "3") (pinfunction "I3_3") (pintype "input"))
    )
    (net (code "191") (name "Net-(IC29D-O)") (class "Default")
      (node (ref "IC29") (pin "11") (pinfunction "O_11") (pintype "output"))
      (node (ref "U$12") (pin "4") (pinfunction "I4_4") (pintype "input"))
    )
    (net (code "192") (name "Net-(IC30A-O)") (class "Default")
      (node (ref "IC30") (pin "3") (pinfunction "O_3") (pintype "output"))
      (node (ref "U$12") (pin "5") (pinfunction "I5_5") (pintype "input"))
    )
    (net (code "193") (name "Net-(IC30B-O)") (class "Default")
      (node (ref "IC30") (pin "6") (pinfunction "O_6") (pintype "output"))
      (node (ref "U$12") (pin "6") (pinfunction "I6_6") (pintype "input"))
    )
    (net (code "194") (name "Net-(IC30C-O)") (class "Default")
      (node (ref "IC30") (pin "8") (pinfunction "O_8") (pintype "output"))
      (node (ref "U$12") (pin "7") (pinfunction "I7_7") (pintype "input"))
    )
    (net (code "195") (name "Net-(IC30D-O)") (class "Default")
      (node (ref "IC30") (pin "11") (pinfunction "O_11") (pintype "output"))
      (node (ref "U$12") (pin "8") (pinfunction "I8_8") (pintype "input"))
    )
    (net (code "196") (name "Net-(IC101A-1CLK)") (class "Default")
      (node (ref "IC101") (pin "25") (pinfunction "2CLK_25") (pintype "input"))
      (node (ref "IC101") (pin "48") (pinfunction "1CLK_48") (pintype "input"))
      (node (ref "X11") (pin "6") (pinfunction "S_6") (pintype "passive"))
    )
    (net (code "197") (name "Net-(IC101A-1D1)") (class "Default")
      (node (ref "IC101") (pin "47") (pinfunction "1D1_47") (pintype "input"))
      (node (ref "X11") (pin "3") (pinfunction "S_3") (pintype "passive"))
    )
    (net (code "198") (name "Net-(IC101A-1D2)") (class "Default")
      (node (ref "IC101") (pin "2") (pinfunction "1Q1_2") (pintype "tri_state"))
      (node (ref "IC101") (pin "46") (pinfunction "1D2_46") (pintype "input"))
      (node (ref "IC22") (pin "10") (pinfunction "I1_10") (pintype "input"))
      (node (ref "IC22") (pin "13") (pinfunction "I1_13") (pintype "input"))
      (node (ref "IC22") (pin "2") (pinfunction "I1_2") (pintype "input"))
      (node (ref "IC22") (pin "5") (pinfunction "I1_5") (pintype "input"))
      (node (ref "IC23") (pin "10") (pinfunction "I1_10") (pintype "input"))
      (node (ref "IC23") (pin "13") (pinfunction "I1_13") (pintype "input"))
      (node (ref "IC23") (pin "2") (pinfunction "I1_2") (pintype "input"))
      (node (ref "IC23") (pin "5") (pinfunction "I1_5") (pintype "input"))
    )
    (net (code "199") (name "Net-(IC101A-1D3)") (class "Default")
      (node (ref "IC101") (pin "3") (pinfunction "1Q2_3") (pintype "tri_state"))
      (node (ref "IC101") (pin "44") (pinfunction "1D3_44") (pintype "input"))
      (node (ref "IC24") (pin "10") (pinfunction "I1_10") (pintype "input"))
      (node (ref "IC24") (pin "13") (pinfunction "I1_13") (pintype "input"))
      (node (ref "IC24") (pin "2") (pinfunction "I1_2") (pintype "input"))
      (node (ref "IC24") (pin "5") (pinfunction "I1_5") (pintype "input"))
      (node (ref "IC25") (pin "10") (pinfunction "I1_10") (pintype "input"))
      (node (ref "IC25") (pin "13") (pinfunction "I1_13") (pintype "input"))
      (node (ref "IC25") (pin "2") (pinfunction "I1_2") (pintype "input"))
      (node (ref "IC25") (pin "5") (pinfunction "I1_5") (pintype "input"))
    )
    (net (code "200") (name "Net-(IC101A-1D4)") (class "Default")
      (node (ref "IC101") (pin "43") (pinfunction "1D4_43") (pintype "input"))
      (node (ref "IC101") (pin "5") (pinfunction "1Q3_5") (pintype "tri_state"))
      (node (ref "IC27") (pin "10") (pinfunction "I1_10") (pintype "input"))
      (node (ref "IC27") (pin "13") (pinfunction "I1_13") (pintype "input"))
      (node (ref "IC27") (pin "2") (pinfunction "I1_2") (pintype "input"))
      (node (ref "IC27") (pin "5") (pinfunction "I1_5") (pintype "input"))
      (node (ref "IC28") (pin "10") (pinfunction "I1_10") (pintype "input"))
      (node (ref "IC28") (pin "13") (pinfunction "I1_13") (pintype "input"))
      (node (ref "IC28") (pin "2") (pinfunction "I1_2") (pintype "input"))
      (node (ref "IC28") (pin "5") (pinfunction "I1_5") (pintype "input"))
    )
    (net (code "201") (name "Net-(IC101A-1D5)") (class "Default")
      (node (ref "IC101") (pin "41") (pinfunction "1D5_41") (pintype "input"))
      (node (ref "IC101") (pin "6") (pinfunction "1Q4_6") (pintype "tri_state"))
      (node (ref "IC29") (pin "10") (pinfunction "I1_10") (pintype "input"))
      (node (ref "IC29") (pin "13") (pinfunction "I1_13") (pintype "input"))
      (node (ref "IC29") (pin "2") (pinfunction "I1_2") (pintype "input"))
      (node (ref "IC29") (pin "5") (pinfunction "I1_5") (pintype "input"))
      (node (ref "IC30") (pin "10") (pinfunction "I1_10") (pintype "input"))
      (node (ref "IC30") (pin "13") (pinfunction "I1_13") (pintype "input"))
      (node (ref "IC30") (pin "2") (pinfunction "I1_2") (pintype "input"))
      (node (ref "IC30") (pin "5") (pinfunction "I1_5") (pintype "input"))
    )
    (net (code "202") (name "Net-(IC101A-1D6)") (class "Default")
      (node (ref "IC10") (pin "10") (pinfunction "I1_10") (pintype "input"))
      (node (ref "IC10") (pin "13") (pinfunction "I1_13") (pintype "input"))
      (node (ref "IC10") (pin "2") (pinfunction "I1_2") (pintype "input"))
      (node (ref "IC10") (pin "5") (pinfunction "I1_5") (pintype "input"))
      (node (ref "IC101") (pin "40") (pinfunction "1D6_40") (pintype "input"))
      (node (ref "IC101") (pin "8") (pinfunction "1Q5_8") (pintype "tri_state"))
      (node (ref "IC7") (pin "10") (pinfunction "I1_10") (pintype "input"))
      (node (ref "IC7") (pin "13") (pinfunction "I1_13") (pintype "input"))
      (node (ref "IC7") (pin "2") (pinfunction "I1_2") (pintype "input"))
      (node (ref "IC7") (pin "5") (pinfunction "I1_5") (pintype "input"))
    )
    (net (code "203") (name "Net-(IC101A-1D7)") (class "Default")
      (node (ref "IC101") (pin "38") (pinfunction "1D7_38") (pintype "input"))
      (node (ref "IC101") (pin "9") (pinfunction "1Q6_9") (pintype "tri_state"))
      (node (ref "IC14") (pin "10") (pinfunction "I1_10") (pintype "input"))
      (node (ref "IC14") (pin "13") (pinfunction "I1_13") (pintype "input"))
      (node (ref "IC14") (pin "2") (pinfunction "I1_2") (pintype "input"))
      (node (ref "IC14") (pin "5") (pinfunction "I1_5") (pintype "input"))
      (node (ref "IC15") (pin "10") (pinfunction "I1_10") (pintype "input"))
      (node (ref "IC15") (pin "13") (pinfunction "I1_13") (pintype "input"))
      (node (ref "IC15") (pin "2") (pinfunction "I1_2") (pintype "input"))
      (node (ref "IC15") (pin "5") (pinfunction "I1_5") (pintype "input"))
    )
    (net (code "204") (name "Net-(IC101A-1D8)") (class "Default")
      (node (ref "IC101") (pin "11") (pinfunction "1Q7_11") (pintype "tri_state"))
      (node (ref "IC101") (pin "37") (pinfunction "1D8_37") (pintype "input"))
      (node (ref "IC17") (pin "10") (pinfunction "I1_10") (pintype "input"))
      (node (ref "IC17") (pin "13") (pinfunction "I1_13") (pintype "input"))
      (node (ref "IC17") (pin "2") (pinfunction "I1_2") (pintype "input"))
      (node (ref "IC17") (pin "5") (pinfunction "I1_5") (pintype "input"))
      (node (ref "IC18") (pin "10") (pinfunction "I1_10") (pintype "input"))
      (node (ref "IC18") (pin "13") (pinfunction "I1_13") (pintype "input"))
      (node (ref "IC18") (pin "2") (pinfunction "I1_2") (pintype "input"))
      (node (ref "IC18") (pin "5") (pinfunction "I1_5") (pintype "input"))
    )
    (net (code "205") (name "Net-(IC101A-1Q8)") (class "Default")
      (node (ref "IC101") (pin "12") (pinfunction "1Q8_12") (pintype "tri_state"))
      (node (ref "IC101") (pin "36") (pinfunction "2D1_36") (pintype "input"))
      (node (ref "IC19") (pin "10") (pinfunction "I1_10") (pintype "input"))
      (node (ref "IC19") (pin "13") (pinfunction "I1_13") (pintype "input"))
      (node (ref "IC19") (pin "2") (pinfunction "I1_2") (pintype "input"))
      (node (ref "IC19") (pin "5") (pinfunction "I1_5") (pintype "input"))
      (node (ref "IC20") (pin "10") (pinfunction "I1_10") (pintype "input"))
      (node (ref "IC20") (pin "13") (pinfunction "I1_13") (pintype "input"))
      (node (ref "IC20") (pin "2") (pinfunction "I1_2") (pintype "input"))
      (node (ref "IC20") (pin "5") (pinfunction "I1_5") (pintype "input"))
    )
    (net (code "206") (name "Net-(IC101A-2D2)") (class "Default")
      (node (ref "IC101") (pin "13") (pinfunction "2Q1_13") (pintype "tri_state"))
      (node (ref "IC101") (pin "35") (pinfunction "2D2_35") (pintype "input"))
      (node (ref "IC2") (pin "10") (pinfunction "I1_10") (pintype "input"))
      (node (ref "IC2") (pin "13") (pinfunction "I1_13") (pintype "input"))
      (node (ref "IC2") (pin "2") (pinfunction "I1_2") (pintype "input"))
      (node (ref "IC2") (pin "5") (pinfunction "I1_5") (pintype "input"))
      (node (ref "IC4") (pin "10") (pinfunction "I1_10") (pintype "input"))
      (node (ref "IC4") (pin "13") (pinfunction "I1_13") (pintype "input"))
      (node (ref "IC4") (pin "2") (pinfunction "I1_2") (pintype "input"))
      (node (ref "IC4") (pin "5") (pinfunction "I1_5") (pintype "input"))
    )
    (net (code "207") (name "Net-(IC101A-2D3)") (class "Default")
      (node (ref "IC101") (pin "14") (pinfunction "2Q2_14") (pintype "tri_state"))
      (node (ref "IC101") (pin "33") (pinfunction "2D3_33") (pintype "input"))
      (node (ref "IC5") (pin "10") (pinfunction "I1_10") (pintype "input"))
      (node (ref "IC5") (pin "13") (pinfunction "I1_13") (pintype "input"))
      (node (ref "IC5") (pin "2") (pinfunction "I1_2") (pintype "input"))
      (node (ref "IC5") (pin "5") (pinfunction "I1_5") (pintype "input"))
      (node (ref "IC6") (pin "10") (pinfunction "I1_10") (pintype "input"))
      (node (ref "IC6") (pin "13") (pinfunction "I1_13") (pintype "input"))
      (node (ref "IC6") (pin "2") (pinfunction "I1_2") (pintype "input"))
      (node (ref "IC6") (pin "5") (pinfunction "I1_5") (pintype "input"))
    )
    (net (code "208") (name "Net-(IC101A-2D4)") (class "Default")
      (node (ref "IC101") (pin "16") (pinfunction "2Q3_16") (pintype "tri_state"))
      (node (ref "IC101") (pin "32") (pinfunction "2D4_32") (pintype "input"))
      (node (ref "IC11") (pin "10") (pinfunction "I1_10") (pintype "input"))
      (node (ref "IC11") (pin "13") (pinfunction "I1_13") (pintype "input"))
      (node (ref "IC11") (pin "2") (pinfunction "I1_2") (pintype "input"))
      (node (ref "IC11") (pin "5") (pinfunction "I1_5") (pintype "input"))
      (node (ref "IC9") (pin "10") (pinfunction "I1_10") (pintype "input"))
      (node (ref "IC9") (pin "13") (pinfunction "I1_13") (pintype "input"))
      (node (ref "IC9") (pin "2") (pinfunction "I1_2") (pintype "input"))
      (node (ref "IC9") (pin "5") (pinfunction "I1_5") (pintype "input"))
    )
    (net (code "209") (name "Net-(IC101A-2Q4)") (class "Default")
      (node (ref "IC101") (pin "17") (pinfunction "2Q4_17") (pintype "tri_state"))
      (node (ref "IC12") (pin "10") (pinfunction "I1_10") (pintype "input"))
      (node (ref "IC12") (pin "13") (pinfunction "I1_13") (pintype "input"))
      (node (ref "IC12") (pin "2") (pinfunction "I1_2") (pintype "input"))
      (node (ref "IC12") (pin "5") (pinfunction "I1_5") (pintype "input"))
      (node (ref "IC13") (pin "10") (pinfunction "I1_10") (pintype "input"))
      (node (ref "IC13") (pin "13") (pinfunction "I1_13") (pintype "input"))
      (node (ref "IC13") (pin "2") (pinfunction "I1_2") (pintype "input"))
      (node (ref "IC13") (pin "5") (pinfunction "I1_5") (pintype "input"))
      (node (ref "X11") (pin "2") (pinfunction "S_2") (pintype "passive"))
    )
    (net (code "210") (name "Net-(U$1-CD+)") (class "Default")
      (node (ref "U$1") (pin "10") (pinfunction "CD+_10") (pintype "passive"))
      (node (ref "U$10") (pin "10") (pinfunction "CD+_10") (pintype "passive"))
      (node (ref "U$11") (pin "10") (pinfunction "CD+_10") (pintype "passive"))
      (node (ref "U$12") (pin "10") (pinfunction "CD+_10") (pintype "passive"))
      (node (ref "U$2") (pin "10") (pinfunction "CD+_10") (pintype "passive"))
      (node (ref "U$3") (pin "10") (pinfunction "CD+_10") (pintype "passive"))
      (node (ref "U$4") (pin "10") (pinfunction "CD+_10") (pintype "passive"))
      (node (ref "U$5") (pin "10") (pinfunction "CD+_10") (pintype "passive"))
      (node (ref "U$6") (pin "10") (pinfunction "CD+_10") (pintype "passive"))
      (node (ref "U$7") (pin "10") (pinfunction "CD+_10") (pintype "passive"))
      (node (ref "U$8") (pin "10") (pinfunction "CD+_10") (pintype "passive"))
      (node (ref "U$9") (pin "10") (pinfunction "CD+_10") (pintype "passive"))
      (node (ref "X11") (pin "7") (pinfunction "S_7") (pintype "passive"))
    )
    (net (code "211") (name "Net-(U$1-O1)") (class "Default")
      (node (ref "U$1") (pin "18") (pinfunction "O1_18") (pintype "open_collector"))
      (node (ref "X2") (pin "1") (pinfunction "S_1") (pintype "passive"))
    )
    (net (code "212") (name "Net-(U$1-O2)") (class "Default")
      (node (ref "U$1") (pin "17") (pinfunction "O2_17") (pintype "open_collector"))
      (node (ref "X2") (pin "3") (pinfunction "S_3") (pintype "passive"))
    )
    (net (code "213") (name "Net-(U$1-O3)") (class "Default")
      (node (ref "U$1") (pin "16") (pinfunction "O3_16") (pintype "open_collector"))
      (node (ref "X2") (pin "5") (pinfunction "S_5") (pintype "passive"))
    )
    (net (code "214") (name "Net-(U$1-O4)") (class "Default")
      (node (ref "U$1") (pin "15") (pinfunction "O4_15") (pintype "open_collector"))
      (node (ref "X2") (pin "7") (pinfunction "S_7") (pintype "passive"))
    )
    (net (code "215") (name "Net-(U$1-O5)") (class "Default")
      (node (ref "U$1") (pin "14") (pinfunction "O5_14") (pintype "open_collector"))
      (node (ref "X2") (pin "9") (pinfunction "S_9") (pintype "passive"))
    )
    (net (code "216") (name "Net-(U$1-O6)") (class "Default")
      (node (ref "U$1") (pin "13") (pinfunction "O6_13") (pintype "open_collector"))
      (node (ref "X2") (pin "11") (pinfunction "S_11") (pintype "passive"))
    )
    (net (code "217") (name "Net-(U$1-O7)") (class "Default")
      (node (ref "U$1") (pin "12") (pinfunction "O7_12") (pintype "open_collector"))
      (node (ref "X2") (pin "13") (pinfunction "S_13") (pintype "passive"))
    )
    (net (code "218") (name "Net-(U$1-O8)") (class "Default")
      (node (ref "U$1") (pin "11") (pinfunction "O8_11") (pintype "open_collector"))
      (node (ref "X2") (pin "15") (pinfunction "S_15") (pintype "passive"))
    )
    (net (code "219") (name "Net-(U$2-O1)") (class "Default")
      (node (ref "U$2") (pin "18") (pinfunction "O1_18") (pintype "open_collector"))
      (node (ref "X2") (pin "17") (pinfunction "S_17") (pintype "passive"))
    )
    (net (code "220") (name "Net-(U$2-O2)") (class "Default")
      (node (ref "U$2") (pin "17") (pinfunction "O2_17") (pintype "open_collector"))
      (node (ref "X2") (pin "19") (pinfunction "S_19") (pintype "passive"))
    )
    (net (code "221") (name "Net-(U$2-O3)") (class "Default")
      (node (ref "U$2") (pin "16") (pinfunction "O3_16") (pintype "open_collector"))
      (node (ref "X2") (pin "21") (pinfunction "S_21") (pintype "passive"))
    )
    (net (code "222") (name "Net-(U$2-O4)") (class "Default")
      (node (ref "U$2") (pin "15") (pinfunction "O4_15") (pintype "open_collector"))
      (node (ref "X2") (pin "23") (pinfunction "S_23") (pintype "passive"))
    )
    (net (code "223") (name "Net-(U$2-O5)") (class "Default")
      (node (ref "U$2") (pin "14") (pinfunction "O5_14") (pintype "open_collector"))
      (node (ref "X2") (pin "25") (pinfunction "S_25") (pintype "passive"))
    )
    (net (code "224") (name "Net-(U$2-O6)") (class "Default")
      (node (ref "U$2") (pin "13") (pinfunction "O6_13") (pintype "open_collector"))
      (node (ref "X2") (pin "27") (pinfunction "S_27") (pintype "passive"))
    )
    (net (code "225") (name "Net-(U$2-O7)") (class "Default")
      (node (ref "U$2") (pin "12") (pinfunction "O7_12") (pintype "open_collector"))
      (node (ref "X2") (pin "29") (pinfunction "S_29") (pintype "passive"))
    )
    (net (code "226") (name "Net-(U$2-O8)") (class "Default")
      (node (ref "U$2") (pin "11") (pinfunction "O8_11") (pintype "open_collector"))
      (node (ref "X2") (pin "31") (pinfunction "S_31") (pintype "passive"))
    )
    (net (code "227") (name "Net-(U$3-O1)") (class "Default")
      (node (ref "U$3") (pin "18") (pinfunction "O1_18") (pintype "open_collector"))
      (node (ref "X2") (pin "2") (pinfunction "S_2") (pintype "passive"))
    )
    (net (code "228") (name "Net-(U$3-O2)") (class "Default")
      (node (ref "U$3") (pin "17") (pinfunction "O2_17") (pintype "open_collector"))
      (node (ref "X2") (pin "4") (pinfunction "S_4") (pintype "passive"))
    )
    (net (code "229") (name "Net-(U$3-O3)") (class "Default")
      (node (ref "U$3") (pin "16") (pinfunction "O3_16") (pintype "open_collector"))
      (node (ref "X2") (pin "6") (pinfunction "S_6") (pintype "passive"))
    )
    (net (code "230") (name "Net-(U$3-O4)") (class "Default")
      (node (ref "U$3") (pin "15") (pinfunction "O4_15") (pintype "open_collector"))
      (node (ref "X2") (pin "8") (pinfunction "S_8") (pintype "passive"))
    )
    (net (code "231") (name "Net-(U$3-O5)") (class "Default")
      (node (ref "U$3") (pin "14") (pinfunction "O5_14") (pintype "open_collector"))
      (node (ref "X2") (pin "10") (pinfunction "S_10") (pintype "passive"))
    )
    (net (code "232") (name "Net-(U$3-O6)") (class "Default")
      (node (ref "U$3") (pin "13") (pinfunction "O6_13") (pintype "open_collector"))
      (node (ref "X2") (pin "12") (pinfunction "S_12") (pintype "passive"))
    )
    (net (code "233") (name "Net-(U$3-O7)") (class "Default")
      (node (ref "U$3") (pin "12") (pinfunction "O7_12") (pintype "open_collector"))
      (node (ref "X2") (pin "14") (pinfunction "S_14") (pintype "passive"))
    )
    (net (code "234") (name "Net-(U$3-O8)") (class "Default")
      (node (ref "U$3") (pin "11") (pinfunction "O8_11") (pintype "open_collector"))
      (node (ref "X2") (pin "16") (pinfunction "S_16") (pintype "passive"))
    )
    (net (code "235") (name "Net-(U$4-O1)") (class "Default")
      (node (ref "U$4") (pin "18") (pinfunction "O1_18") (pintype "open_collector"))
      (node (ref "X2") (pin "18") (pinfunction "S_18") (pintype "passive"))
    )
    (net (code "236") (name "Net-(U$4-O2)") (class "Default")
      (node (ref "U$4") (pin "17") (pinfunction "O2_17") (pintype "open_collector"))
      (node (ref "X2") (pin "20") (pinfunction "S_20") (pintype "passive"))
    )
    (net (code "237") (name "Net-(U$4-O3)") (class "Default")
      (node (ref "U$4") (pin "16") (pinfunction "O3_16") (pintype "open_collector"))
      (node (ref "X2") (pin "22") (pinfunction "S_22") (pintype "passive"))
    )
    (net (code "238") (name "Net-(U$4-O4)") (class "Default")
      (node (ref "U$4") (pin "15") (pinfunction "O4_15") (pintype "open_collector"))
      (node (ref "X2") (pin "24") (pinfunction "S_24") (pintype "passive"))
    )
    (net (code "239") (name "Net-(U$4-O5)") (class "Default")
      (node (ref "U$4") (pin "14") (pinfunction "O5_14") (pintype "open_collector"))
      (node (ref "X2") (pin "26") (pinfunction "S_26") (pintype "passive"))
    )
    (net (code "240") (name "Net-(U$4-O6)") (class "Default")
      (node (ref "U$4") (pin "13") (pinfunction "O6_13") (pintype "open_collector"))
      (node (ref "X2") (pin "28") (pinfunction "S_28") (pintype "passive"))
    )
    (net (code "241") (name "Net-(U$4-O7)") (class "Default")
      (node (ref "U$4") (pin "12") (pinfunction "O7_12") (pintype "open_collector"))
      (node (ref "X2") (pin "30") (pinfunction "S_30") (pintype "passive"))
    )
    (net (code "242") (name "Net-(U$4-O8)") (class "Default")
      (node (ref "U$4") (pin "11") (pinfunction "O8_11") (pintype "open_collector"))
      (node (ref "X2") (pin "32") (pinfunction "S_32") (pintype "passive"))
    )
    (net (code "243") (name "Net-(U$5-O1)") (class "Default")
      (node (ref "U$5") (pin "18") (pinfunction "O1_18") (pintype "open_collector"))
      (node (ref "X1") (pin "1") (pinfunction "S_1") (pintype "passive"))
    )
    (net (code "244") (name "Net-(U$5-O2)") (class "Default")
      (node (ref "U$5") (pin "17") (pinfunction "O2_17") (pintype "open_collector"))
      (node (ref "X1") (pin "3") (pinfunction "S_3") (pintype "passive"))
    )
    (net (code "245") (name "Net-(U$5-O3)") (class "Default")
      (node (ref "U$5") (pin "16") (pinfunction "O3_16") (pintype "open_collector"))
      (node (ref "X1") (pin "5") (pinfunction "S_5") (pintype "passive"))
    )
    (net (code "246") (name "Net-(U$5-O4)") (class "Default")
      (node (ref "U$5") (pin "15") (pinfunction "O4_15") (pintype "open_collector"))
      (node (ref "X1") (pin "7") (pinfunction "S_7") (pintype "passive"))
    )
    (net (code "247") (name "Net-(U$5-O5)") (class "Default")
      (node (ref "U$5") (pin "14") (pinfunction "O5_14") (pintype "open_collector"))
      (node (ref "X1") (pin "9") (pinfunction "S_9") (pintype "passive"))
    )
    (net (code "248") (name "Net-(U$5-O6)") (class "Default")
      (node (ref "U$5") (pin "13") (pinfunction "O6_13") (pintype "open_collector"))
      (node (ref "X1") (pin "11") (pinfunction "S_11") (pintype "passive"))
    )
    (net (code "249") (name "Net-(U$5-O7)") (class "Default")
      (node (ref "U$5") (pin "12") (pinfunction "O7_12") (pintype "open_collector"))
      (node (ref "X1") (pin "13") (pinfunction "S_13") (pintype "passive"))
    )
    (net (code "250") (name "Net-(U$5-O8)") (class "Default")
      (node (ref "U$5") (pin "11") (pinfunction "O8_11") (pintype "open_collector"))
      (node (ref "X1") (pin "15") (pinfunction "S_15") (pintype "passive"))
    )
    (net (code "251") (name "Net-(U$6-O1)") (class "Default")
      (node (ref "U$6") (pin "18") (pinfunction "O1_18") (pintype "open_collector"))
      (node (ref "X1") (pin "17") (pinfunction "S_17") (pintype "passive"))
    )
    (net (code "252") (name "Net-(U$6-O2)") (class "Default")
      (node (ref "U$6") (pin "17") (pinfunction "O2_17") (pintype "open_collector"))
      (node (ref "X1") (pin "19") (pinfunction "S_19") (pintype "passive"))
    )
    (net (code "253") (name "Net-(U$6-O3)") (class "Default")
      (node (ref "U$6") (pin "16") (pinfunction "O3_16") (pintype "open_collector"))
      (node (ref "X1") (pin "21") (pinfunction "S_21") (pintype "passive"))
    )
    (net (code "254") (name "Net-(U$6-O4)") (class "Default")
      (node (ref "U$6") (pin "15") (pinfunction "O4_15") (pintype "open_collector"))
      (node (ref "X1") (pin "23") (pinfunction "S_23") (pintype "passive"))
    )
    (net (code "255") (name "Net-(U$6-O5)") (class "Default")
      (node (ref "U$6") (pin "14") (pinfunction "O5_14") (pintype "open_collector"))
      (node (ref "X1") (pin "25") (pinfunction "S_25") (pintype "passive"))
    )
    (net (code "256") (name "Net-(U$6-O6)") (class "Default")
      (node (ref "U$6") (pin "13") (pinfunction "O6_13") (pintype "open_collector"))
      (node (ref "X1") (pin "27") (pinfunction "S_27") (pintype "passive"))
    )
    (net (code "257") (name "Net-(U$6-O7)") (class "Default")
      (node (ref "U$6") (pin "12") (pinfunction "O7_12") (pintype "open_collector"))
      (node (ref "X1") (pin "29") (pinfunction "S_29") (pintype "passive"))
    )
    (net (code "258") (name "Net-(U$6-O8)") (class "Default")
      (node (ref "U$6") (pin "11") (pinfunction "O8_11") (pintype "open_collector"))
      (node (ref "X1") (pin "31") (pinfunction "S_31") (pintype "passive"))
    )
    (net (code "259") (name "Net-(U$7-O1)") (class "Default")
      (node (ref "U$7") (pin "18") (pinfunction "O1_18") (pintype "open_collector"))
      (node (ref "X1") (pin "2") (pinfunction "S_2") (pintype "passive"))
    )
    (net (code "260") (name "Net-(U$7-O2)") (class "Default")
      (node (ref "U$7") (pin "17") (pinfunction "O2_17") (pintype "open_collector"))
      (node (ref "X1") (pin "4") (pinfunction "S_4") (pintype "passive"))
    )
    (net (code "261") (name "Net-(U$7-O3)") (class "Default")
      (node (ref "U$7") (pin "16") (pinfunction "O3_16") (pintype "open_collector"))
      (node (ref "X1") (pin "6") (pinfunction "S_6") (pintype "passive"))
    )
    (net (code "262") (name "Net-(U$7-O4)") (class "Default")
      (node (ref "U$7") (pin "15") (pinfunction "O4_15") (pintype "open_collector"))
      (node (ref "X1") (pin "8") (pinfunction "S_8") (pintype "passive"))
    )
    (net (code "263") (name "Net-(U$7-O5)") (class "Default")
      (node (ref "U$7") (pin "14") (pinfunction "O5_14") (pintype "open_collector"))
      (node (ref "X1") (pin "10") (pinfunction "S_10") (pintype "passive"))
    )
    (net (code "264") (name "Net-(U$7-O6)") (class "Default")
      (node (ref "U$7") (pin "13") (pinfunction "O6_13") (pintype "open_collector"))
      (node (ref "X1") (pin "12") (pinfunction "S_12") (pintype "passive"))
    )
    (net (code "265") (name "Net-(U$7-O7)") (class "Default")
      (node (ref "U$7") (pin "12") (pinfunction "O7_12") (pintype "open_collector"))
      (node (ref "X1") (pin "14") (pinfunction "S_14") (pintype "passive"))
    )
    (net (code "266") (name "Net-(U$7-O8)") (class "Default")
      (node (ref "U$7") (pin "11") (pinfunction "O8_11") (pintype "open_collector"))
      (node (ref "X1") (pin "16") (pinfunction "S_16") (pintype "passive"))
    )
    (net (code "267") (name "Net-(U$8-O1)") (class "Default")
      (node (ref "U$8") (pin "18") (pinfunction "O1_18") (pintype "open_collector"))
      (node (ref "X1") (pin "18") (pinfunction "S_18") (pintype "passive"))
    )
    (net (code "268") (name "Net-(U$8-O2)") (class "Default")
      (node (ref "U$8") (pin "17") (pinfunction "O2_17") (pintype "open_collector"))
      (node (ref "X1") (pin "20") (pinfunction "S_20") (pintype "passive"))
    )
    (net (code "269") (name "Net-(U$8-O3)") (class "Default")
      (node (ref "U$8") (pin "16") (pinfunction "O3_16") (pintype "open_collector"))
      (node (ref "X1") (pin "22") (pinfunction "S_22") (pintype "passive"))
    )
    (net (code "270") (name "Net-(U$8-O4)") (class "Default")
      (node (ref "U$8") (pin "15") (pinfunction "O4_15") (pintype "open_collector"))
      (node (ref "X1") (pin "24") (pinfunction "S_24") (pintype "passive"))
    )
    (net (code "271") (name "Net-(U$8-O5)") (class "Default")
      (node (ref "U$8") (pin "14") (pinfunction "O5_14") (pintype "open_collector"))
      (node (ref "X1") (pin "26") (pinfunction "S_26") (pintype "passive"))
    )
    (net (code "272") (name "Net-(U$8-O6)") (class "Default")
      (node (ref "U$8") (pin "13") (pinfunction "O6_13") (pintype "open_collector"))
      (node (ref "X1") (pin "28") (pinfunction "S_28") (pintype "passive"))
    )
    (net (code "273") (name "Net-(U$8-O7)") (class "Default")
      (node (ref "U$8") (pin "12") (pinfunction "O7_12") (pintype "open_collector"))
      (node (ref "X1") (pin "30") (pinfunction "S_30") (pintype "passive"))
    )
    (net (code "274") (name "Net-(U$8-O8)") (class "Default")
      (node (ref "U$8") (pin "11") (pinfunction "O8_11") (pintype "open_collector"))
      (node (ref "X1") (pin "32") (pinfunction "S_32") (pintype "passive"))
    )
    (net (code "275") (name "Net-(U$9-O1)") (class "Default")
      (node (ref "U$9") (pin "18") (pinfunction "O1_18") (pintype "open_collector"))
      (node (ref "X3") (pin "1") (pinfunction "S_1") (pintype "passive"))
    )
    (net (code "276") (name "Net-(U$9-O2)") (class "Default")
      (node (ref "U$9") (pin "17") (pinfunction "O2_17") (pintype "open_collector"))
      (node (ref "X3") (pin "3") (pinfunction "S_3") (pintype "passive"))
    )
    (net (code "277") (name "Net-(U$9-O3)") (class "Default")
      (node (ref "U$9") (pin "16") (pinfunction "O3_16") (pintype "open_collector"))
      (node (ref "X3") (pin "5") (pinfunction "S_5") (pintype "passive"))
    )
    (net (code "278") (name "Net-(U$9-O4)") (class "Default")
      (node (ref "U$9") (pin "15") (pinfunction "O4_15") (pintype "open_collector"))
      (node (ref "X3") (pin "7") (pinfunction "S_7") (pintype "passive"))
    )
    (net (code "279") (name "Net-(U$9-O5)") (class "Default")
      (node (ref "U$9") (pin "14") (pinfunction "O5_14") (pintype "open_collector"))
      (node (ref "X3") (pin "9") (pinfunction "S_9") (pintype "passive"))
    )
    (net (code "280") (name "Net-(U$9-O6)") (class "Default")
      (node (ref "U$9") (pin "13") (pinfunction "O6_13") (pintype "open_collector"))
      (node (ref "X3") (pin "11") (pinfunction "S_11") (pintype "passive"))
    )
    (net (code "281") (name "Net-(U$9-O7)") (class "Default")
      (node (ref "U$9") (pin "12") (pinfunction "O7_12") (pintype "open_collector"))
      (node (ref "X3") (pin "13") (pinfunction "S_13") (pintype "passive"))
    )
    (net (code "282") (name "Net-(U$9-O8)") (class "Default")
      (node (ref "U$9") (pin "11") (pinfunction "O8_11") (pintype "open_collector"))
      (node (ref "X3") (pin "15") (pinfunction "S_15") (pintype "passive"))
    )
    (net (code "283") (name "Net-(U$10-O1)") (class "Default")
      (node (ref "U$10") (pin "18") (pinfunction "O1_18") (pintype "open_collector"))
      (node (ref "X3") (pin "17") (pinfunction "S_17") (pintype "passive"))
    )
    (net (code "284") (name "Net-(U$10-O2)") (class "Default")
      (node (ref "U$10") (pin "17") (pinfunction "O2_17") (pintype "open_collector"))
      (node (ref "X3") (pin "19") (pinfunction "S_19") (pintype "passive"))
    )
    (net (code "285") (name "Net-(U$10-O3)") (class "Default")
      (node (ref "U$10") (pin "16") (pinfunction "O3_16") (pintype "open_collector"))
      (node (ref "X3") (pin "21") (pinfunction "S_21") (pintype "passive"))
    )
    (net (code "286") (name "Net-(U$10-O4)") (class "Default")
      (node (ref "U$10") (pin "15") (pinfunction "O4_15") (pintype "open_collector"))
      (node (ref "X3") (pin "23") (pinfunction "S_23") (pintype "passive"))
    )
    (net (code "287") (name "Net-(U$10-O5)") (class "Default")
      (node (ref "U$10") (pin "14") (pinfunction "O5_14") (pintype "open_collector"))
      (node (ref "X3") (pin "25") (pinfunction "S_25") (pintype "passive"))
    )
    (net (code "288") (name "Net-(U$10-O6)") (class "Default")
      (node (ref "U$10") (pin "13") (pinfunction "O6_13") (pintype "open_collector"))
      (node (ref "X3") (pin "27") (pinfunction "S_27") (pintype "passive"))
    )
    (net (code "289") (name "Net-(U$10-O7)") (class "Default")
      (node (ref "U$10") (pin "12") (pinfunction "O7_12") (pintype "open_collector"))
      (node (ref "X3") (pin "29") (pinfunction "S_29") (pintype "passive"))
    )
    (net (code "290") (name "Net-(U$10-O8)") (class "Default")
      (node (ref "U$10") (pin "11") (pinfunction "O8_11") (pintype "open_collector"))
      (node (ref "X3") (pin "31") (pinfunction "S_31") (pintype "passive"))
    )
    (net (code "291") (name "Net-(U$11-O1)") (class "Default")
      (node (ref "U$11") (pin "18") (pinfunction "O1_18") (pintype "open_collector"))
      (node (ref "X3") (pin "2") (pinfunction "S_2") (pintype "passive"))
    )
    (net (code "292") (name "Net-(U$11-O2)") (class "Default")
      (node (ref "U$11") (pin "17") (pinfunction "O2_17") (pintype "open_collector"))
      (node (ref "X3") (pin "4") (pinfunction "S_4") (pintype "passive"))
    )
    (net (code "293") (name "Net-(U$11-O3)") (class "Default")
      (node (ref "U$11") (pin "16") (pinfunction "O3_16") (pintype "open_collector"))
      (node (ref "X3") (pin "6") (pinfunction "S_6") (pintype "passive"))
    )
    (net (code "294") (name "Net-(U$11-O4)") (class "Default")
      (node (ref "U$11") (pin "15") (pinfunction "O4_15") (pintype "open_collector"))
      (node (ref "X3") (pin "8") (pinfunction "S_8") (pintype "passive"))
    )
    (net (code "295") (name "Net-(U$11-O5)") (class "Default")
      (node (ref "U$11") (pin "14") (pinfunction "O5_14") (pintype "open_collector"))
      (node (ref "X3") (pin "10") (pinfunction "S_10") (pintype "passive"))
    )
    (net (code "296") (name "Net-(U$11-O6)") (class "Default")
      (node (ref "U$11") (pin "13") (pinfunction "O6_13") (pintype "open_collector"))
      (node (ref "X3") (pin "12") (pinfunction "S_12") (pintype "passive"))
    )
    (net (code "297") (name "Net-(U$11-O7)") (class "Default")
      (node (ref "U$11") (pin "12") (pinfunction "O7_12") (pintype "open_collector"))
      (node (ref "X3") (pin "14") (pinfunction "S_14") (pintype "passive"))
    )
    (net (code "298") (name "Net-(U$11-O8)") (class "Default")
      (node (ref "U$11") (pin "11") (pinfunction "O8_11") (pintype "open_collector"))
      (node (ref "X3") (pin "16") (pinfunction "S_16") (pintype "passive"))
    )
    (net (code "299") (name "Net-(U$12-O1)") (class "Default")
      (node (ref "U$12") (pin "18") (pinfunction "O1_18") (pintype "open_collector"))
      (node (ref "X3") (pin "18") (pinfunction "S_18") (pintype "passive"))
    )
    (net (code "300") (name "Net-(U$12-O2)") (class "Default")
      (node (ref "U$12") (pin "17") (pinfunction "O2_17") (pintype "open_collector"))
      (node (ref "X3") (pin "20") (pinfunction "S_20") (pintype "passive"))
    )
    (net (code "301") (name "Net-(U$12-O3)") (class "Default")
      (node (ref "U$12") (pin "16") (pinfunction "O3_16") (pintype "open_collector"))
      (node (ref "X3") (pin "22") (pinfunction "S_22") (pintype "passive"))
    )
    (net (code "302") (name "Net-(U$12-O4)") (class "Default")
      (node (ref "U$12") (pin "15") (pinfunction "O4_15") (pintype "open_collector"))
      (node (ref "X3") (pin "24") (pinfunction "S_24") (pintype "passive"))
    )
    (net (code "303") (name "Net-(U$12-O5)") (class "Default")
      (node (ref "U$12") (pin "14") (pinfunction "O5_14") (pintype "open_collector"))
      (node (ref "X3") (pin "26") (pinfunction "S_26") (pintype "passive"))
    )
    (net (code "304") (name "Net-(U$12-O6)") (class "Default")
      (node (ref "U$12") (pin "13") (pinfunction "O6_13") (pintype "open_collector"))
      (node (ref "X3") (pin "28") (pinfunction "S_28") (pintype "passive"))
    )
    (net (code "305") (name "Net-(U$12-O7)") (class "Default")
      (node (ref "U$12") (pin "12") (pinfunction "O7_12") (pintype "open_collector"))
      (node (ref "X3") (pin "30") (pinfunction "S_30") (pintype "passive"))
    )
    (net (code "306") (name "Net-(U$12-O8)") (class "Default")
      (node (ref "U$12") (pin "11") (pinfunction "O8_11") (pintype "open_collector"))
      (node (ref "X3") (pin "32") (pinfunction "S_32") (pintype "passive"))
    )
    (net (code "307") (name "VCC") (class "Default")
      (node (ref "X11") (pin "8") (pinfunction "S_8") (pintype "passive"))
    )
    (net (code "308") (name "unconnected-(IC101A-2D5-Pad30)") (class "Default")
      (node (ref "IC101") (pin "30") (pinfunction "2D5_30") (pintype "input"))
    )
    (net (code "309") (name "unconnected-(IC101A-2D6-Pad29)") (class "Default")
      (node (ref "IC101") (pin "29") (pinfunction "2D6_29") (pintype "input"))
    )
    (net (code "310") (name "unconnected-(IC101A-2D7-Pad27)") (class "Default")
      (node (ref "IC101") (pin "27") (pinfunction "2D7_27") (pintype "input"))
    )
    (net (code "311") (name "unconnected-(IC101A-2D8-Pad26)") (class "Default")
      (node (ref "IC101") (pin "26") (pinfunction "2D8_26") (pintype "input"))
    )
    (net (code "312") (name "unconnected-(IC101A-2Q5-Pad19)") (class "Default")
      (node (ref "IC101") (pin "19") (pinfunction "2Q5_19") (pintype "tri_state"))
    )
    (net (code "313") (name "unconnected-(IC101A-2Q6-Pad20)") (class "Default")
      (node (ref "IC101") (pin "20") (pinfunction "2Q6_20") (pintype "tri_state"))
    )
    (net (code "314") (name "unconnected-(IC101A-2Q7-Pad22)") (class "Default")
      (node (ref "IC101") (pin "22") (pinfunction "2Q7_22") (pintype "tri_state"))
    )
    (net (code "315") (name "unconnected-(IC101A-2Q8-Pad23)") (class "Default")
      (node (ref "IC101") (pin "23") (pinfunction "2Q8_23") (pintype "tri_state"))
    )
    (net (code "316") (name "unconnected-(X11B-S-Pad10)") (class "Default")
      (node (ref "X11") (pin "10") (pinfunction "S_10") (pintype "passive"))
    )
    (net (code "317") (name "unconnected-(X11C-S-Pad11)") (class "Default")
      (node (ref "X11") (pin "11") (pinfunction "S_11") (pintype "passive"))
    )
    (net (code "318") (name "unconnected-(X11D-S-Pad12)") (class "Default")
      (node (ref "X11") (pin "12") (pinfunction "S_12") (pintype "passive"))
    )
    (net (code "319") (name "unconnected-(X11E-S-Pad13)") (class "Default")
      (node (ref "X11") (pin "13") (pinfunction "S_13") (pintype "passive"))
    )
    (net (code "320") (name "unconnected-(X11F-S-Pad14)") (class "Default")
      (node (ref "X11") (pin "14") (pinfunction "S_14") (pintype "passive"))
    )
  )
)
